# main.net
KiCad netlist of a schematic drawn in EAGLE
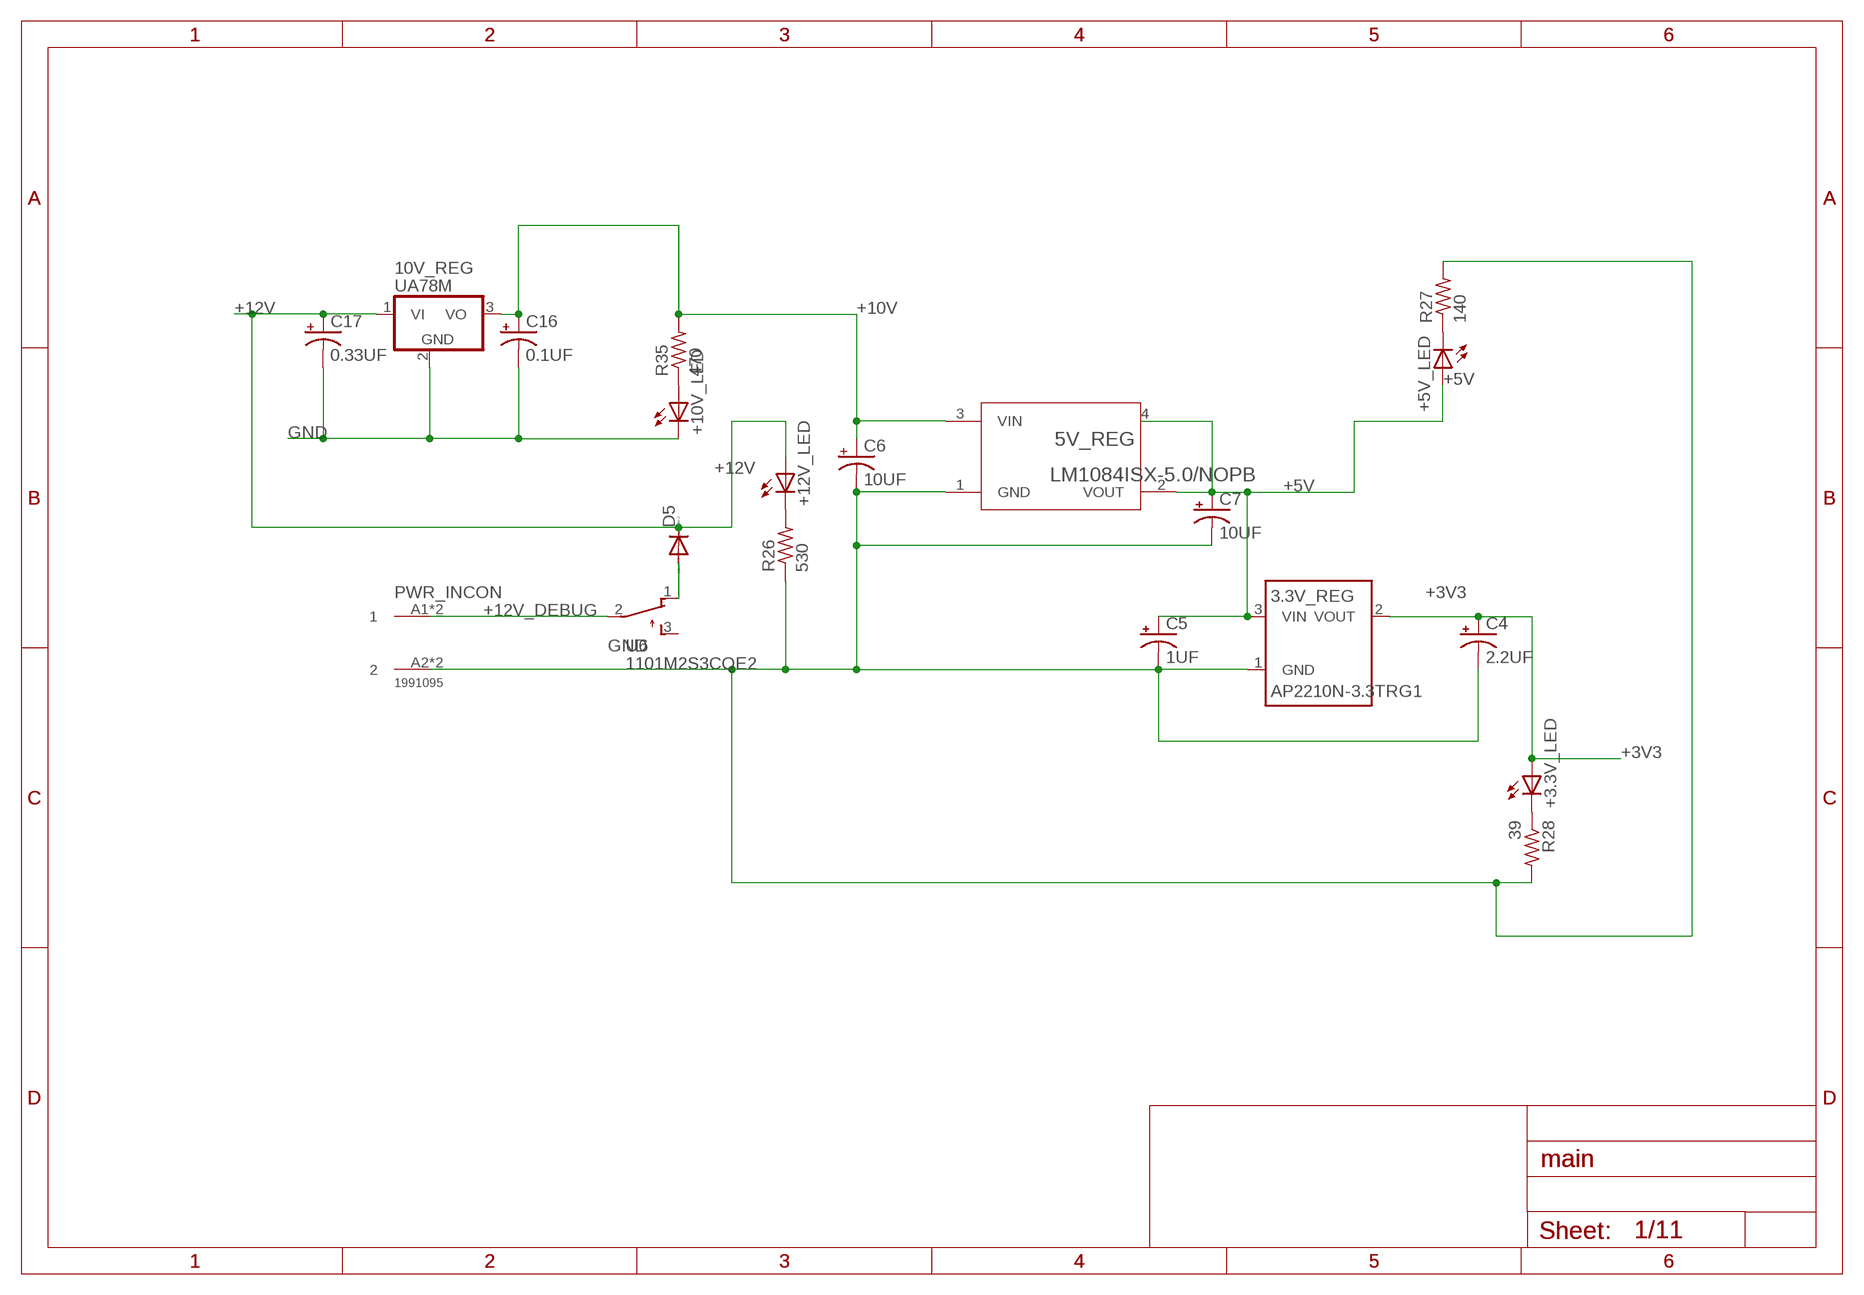
[diagram p0: schematic, sheet 1]
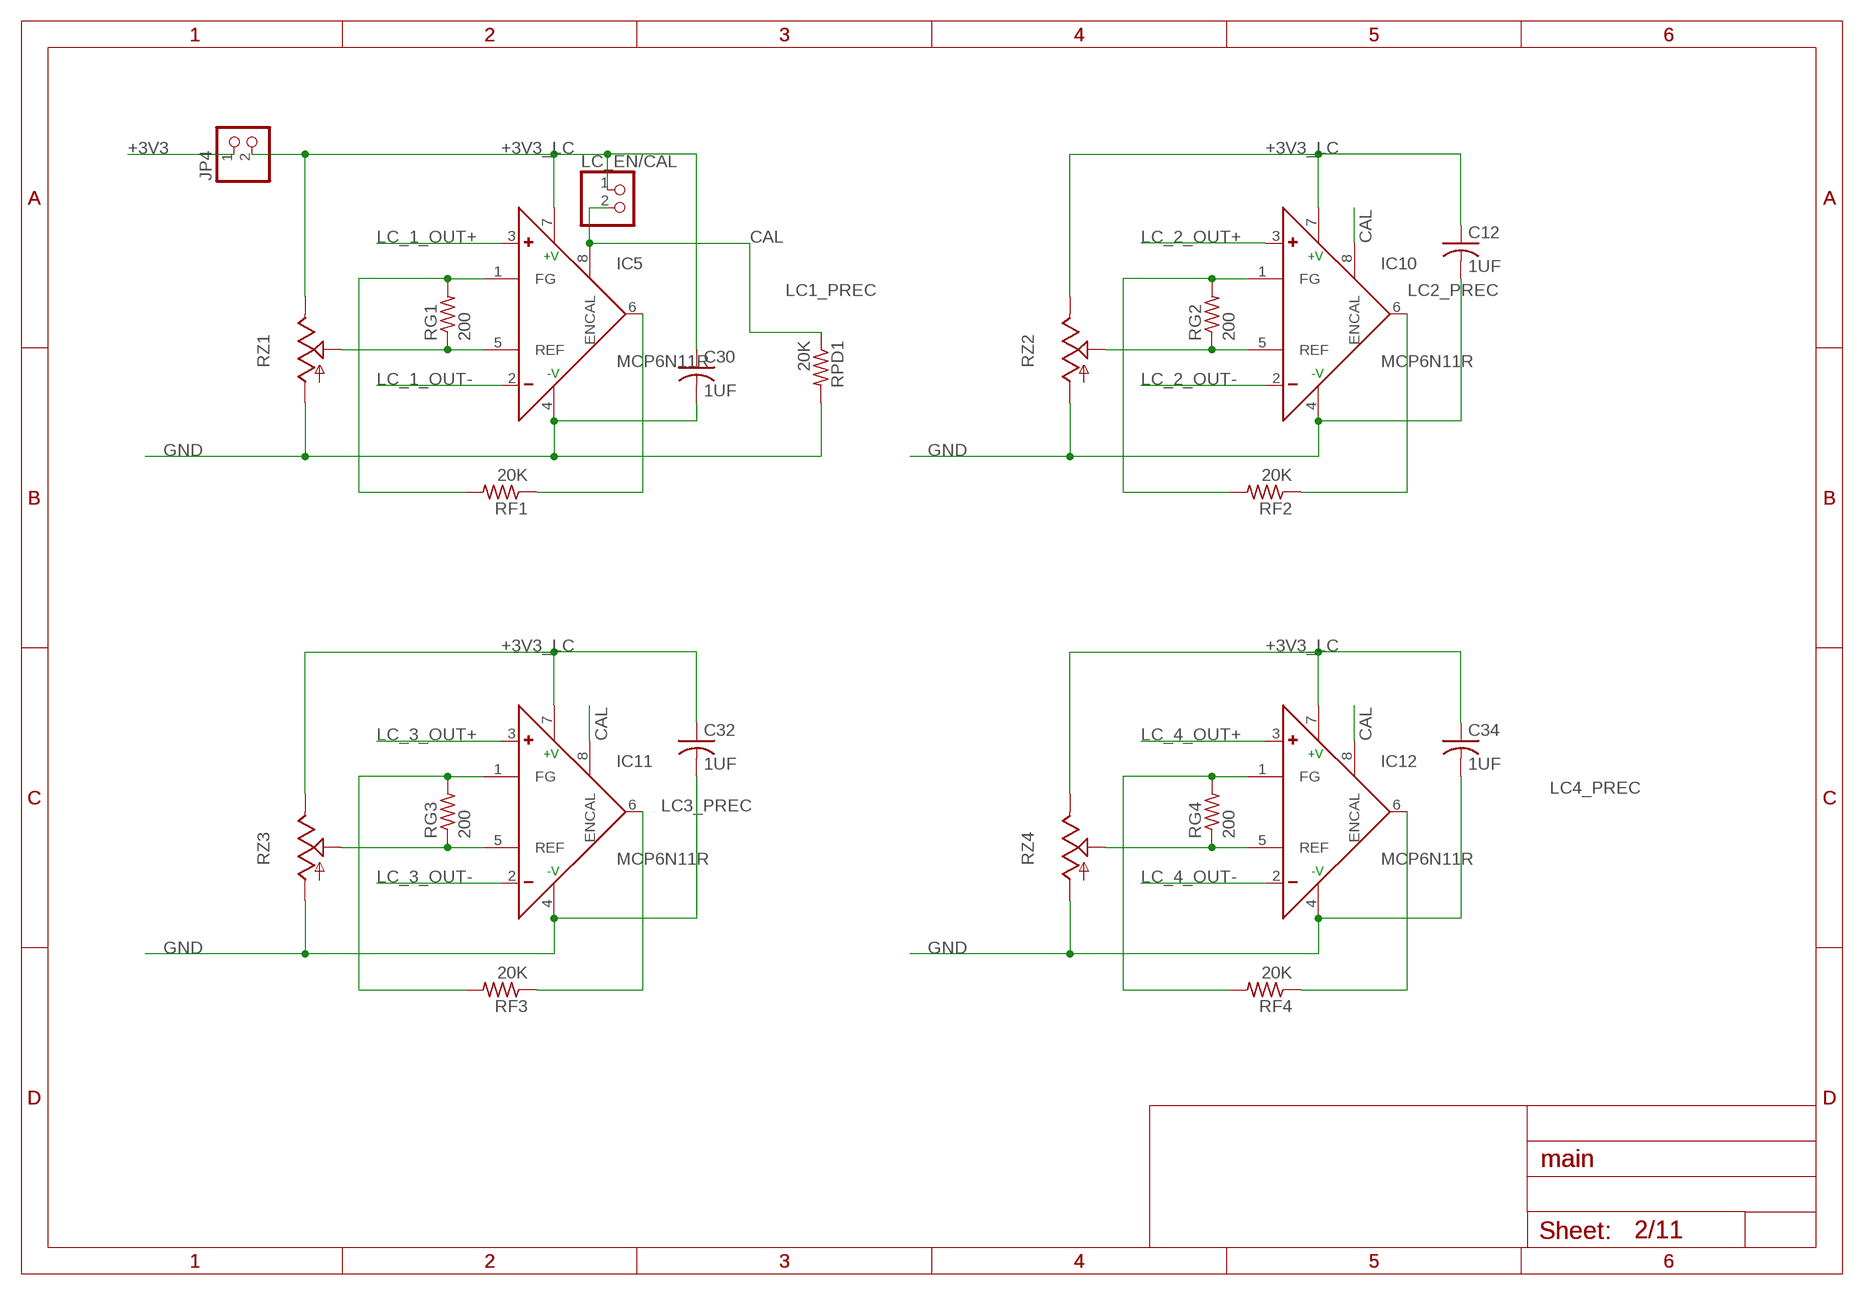
[diagram p1: schematic, sheet 2]
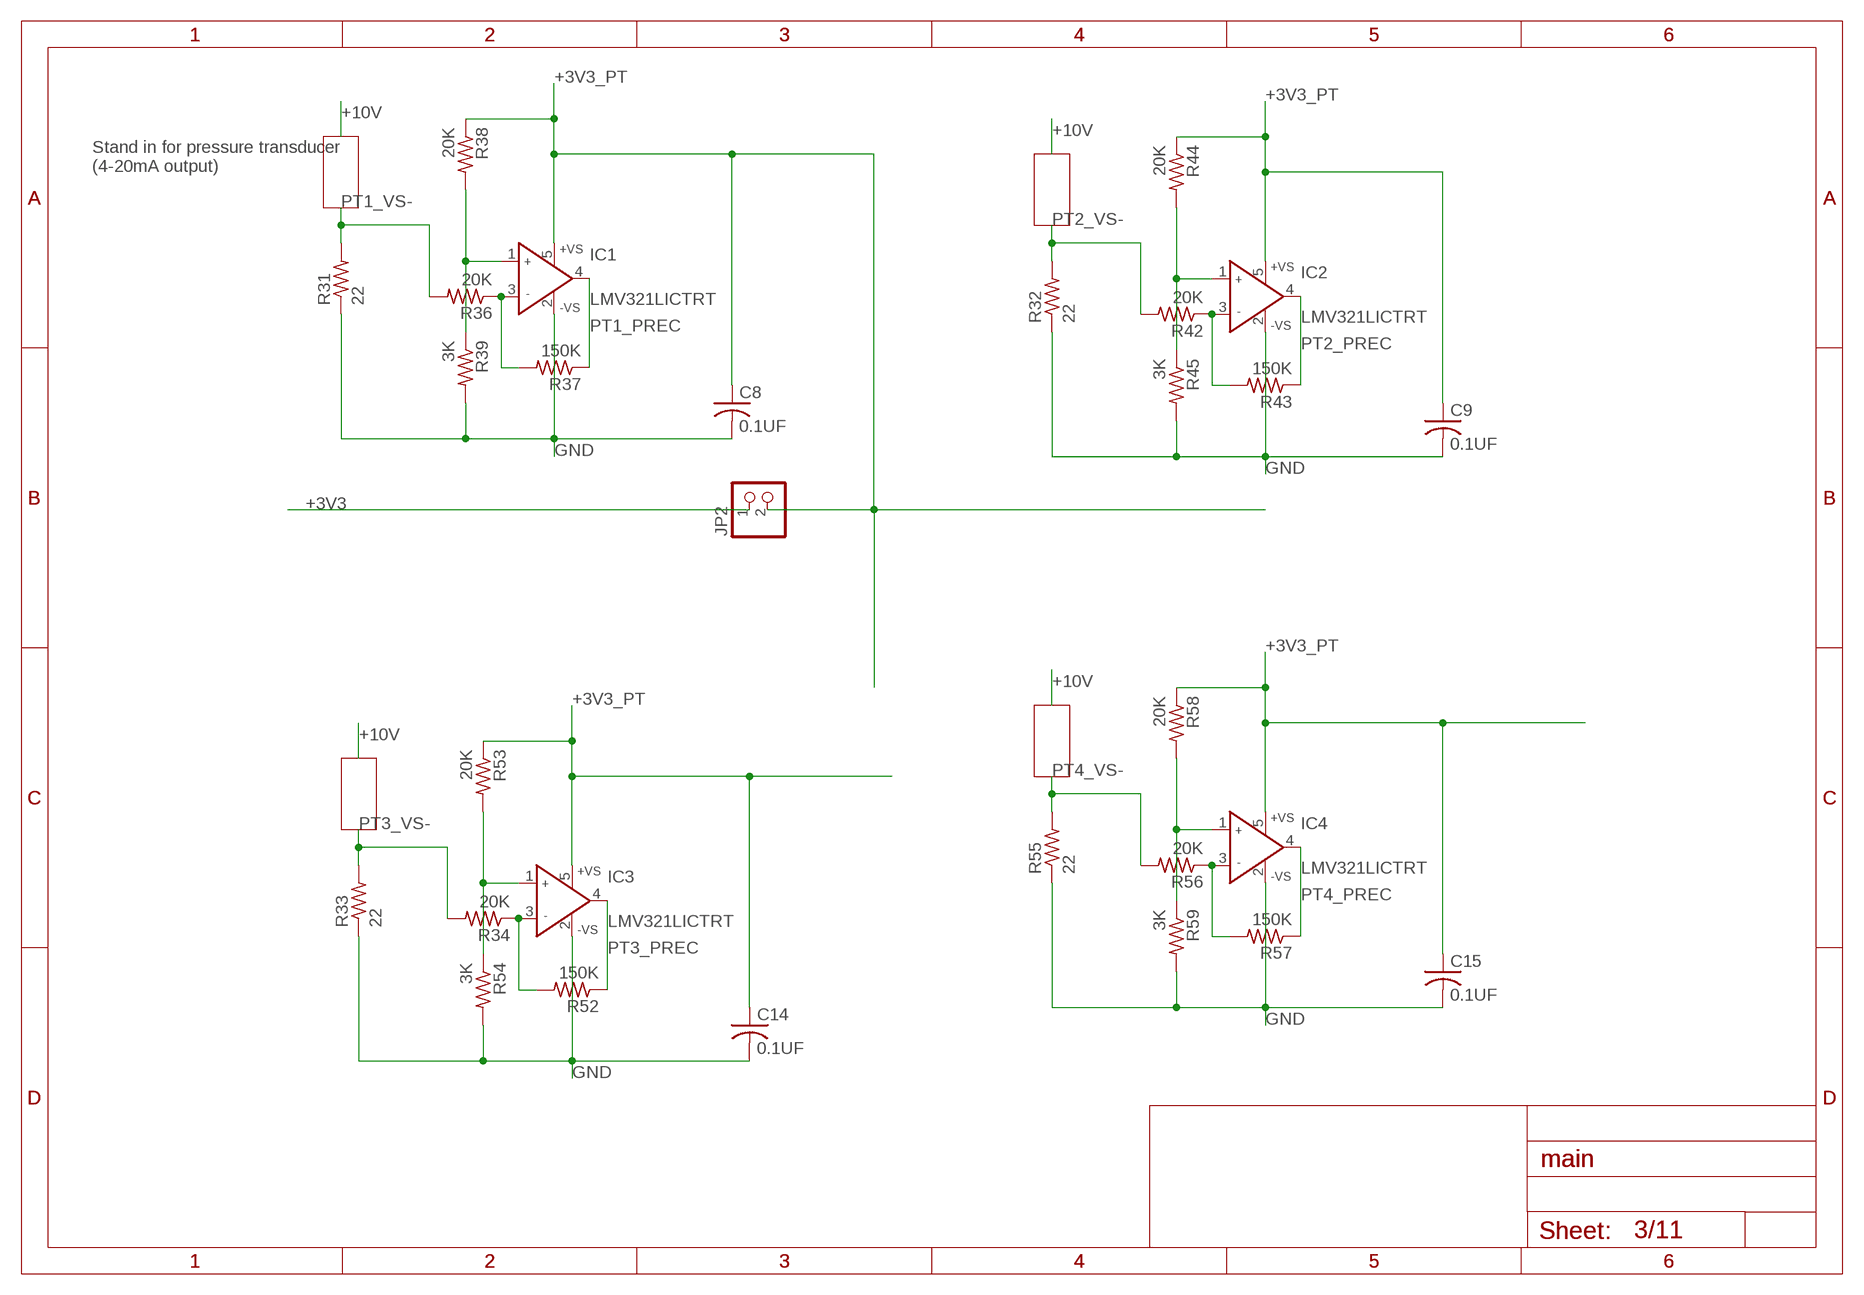
[diagram p2: schematic, sheet 3]
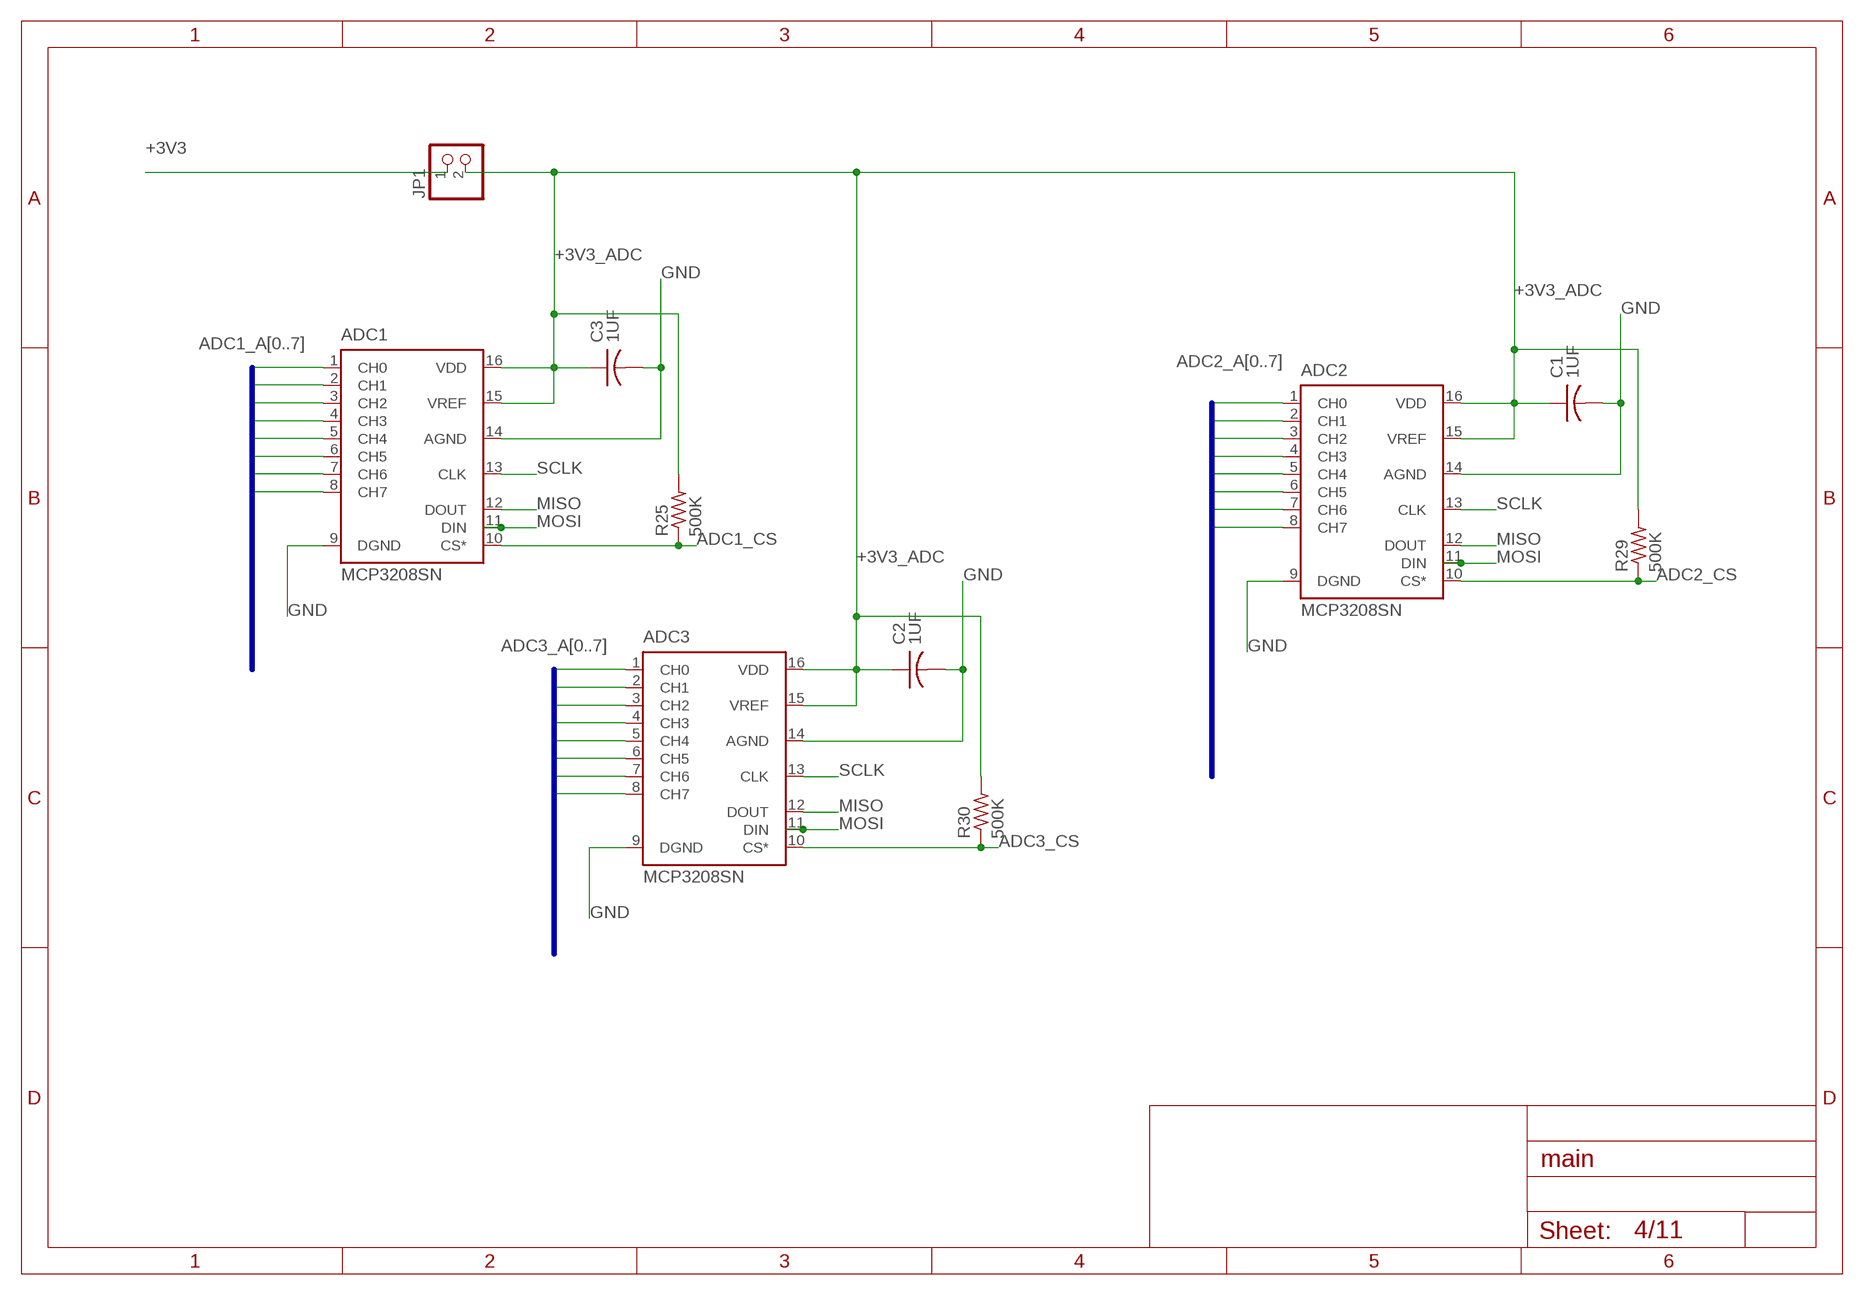
[diagram p3: schematic, sheet 4]
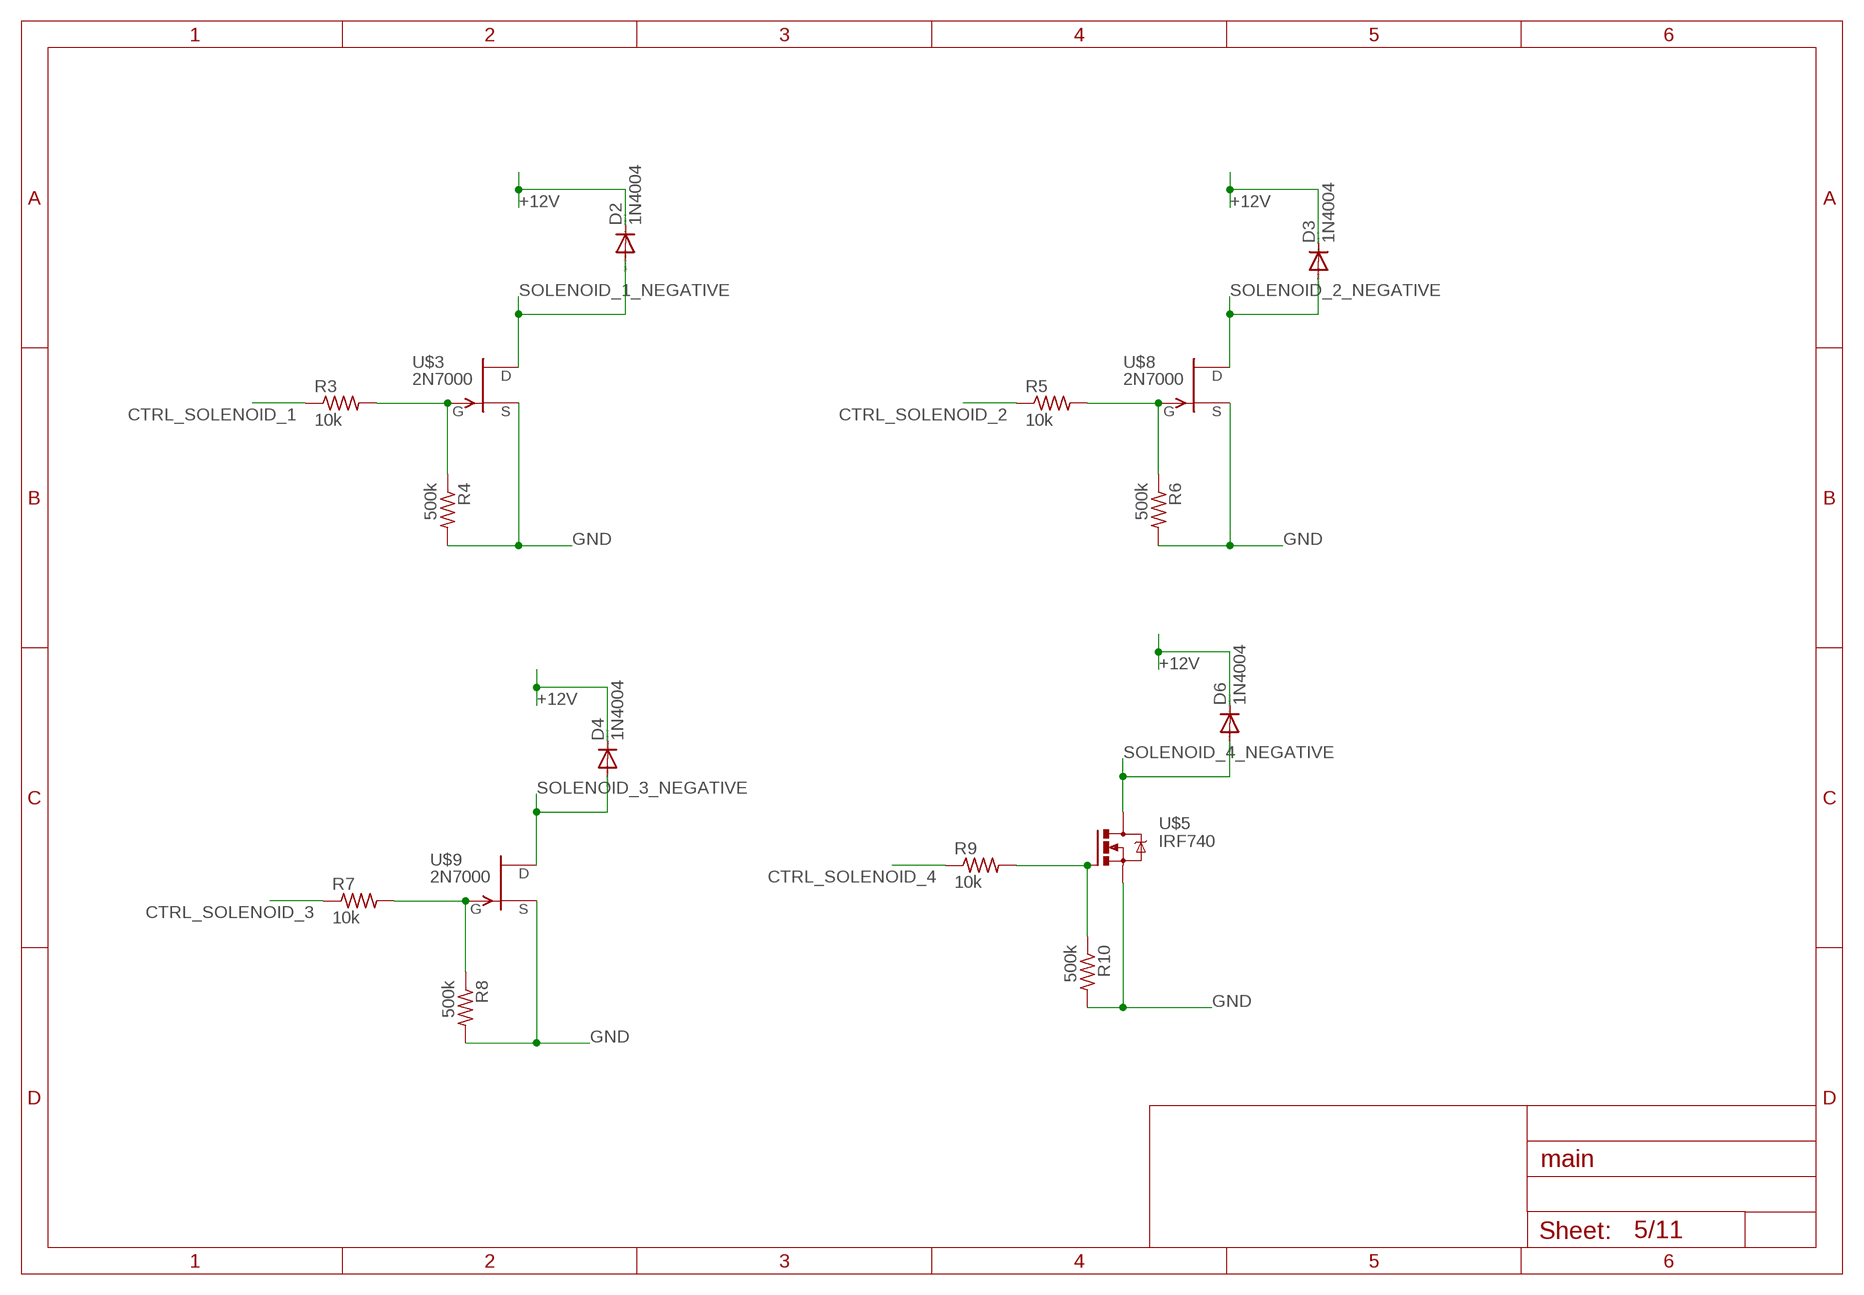
[diagram p4: schematic, sheet 5]
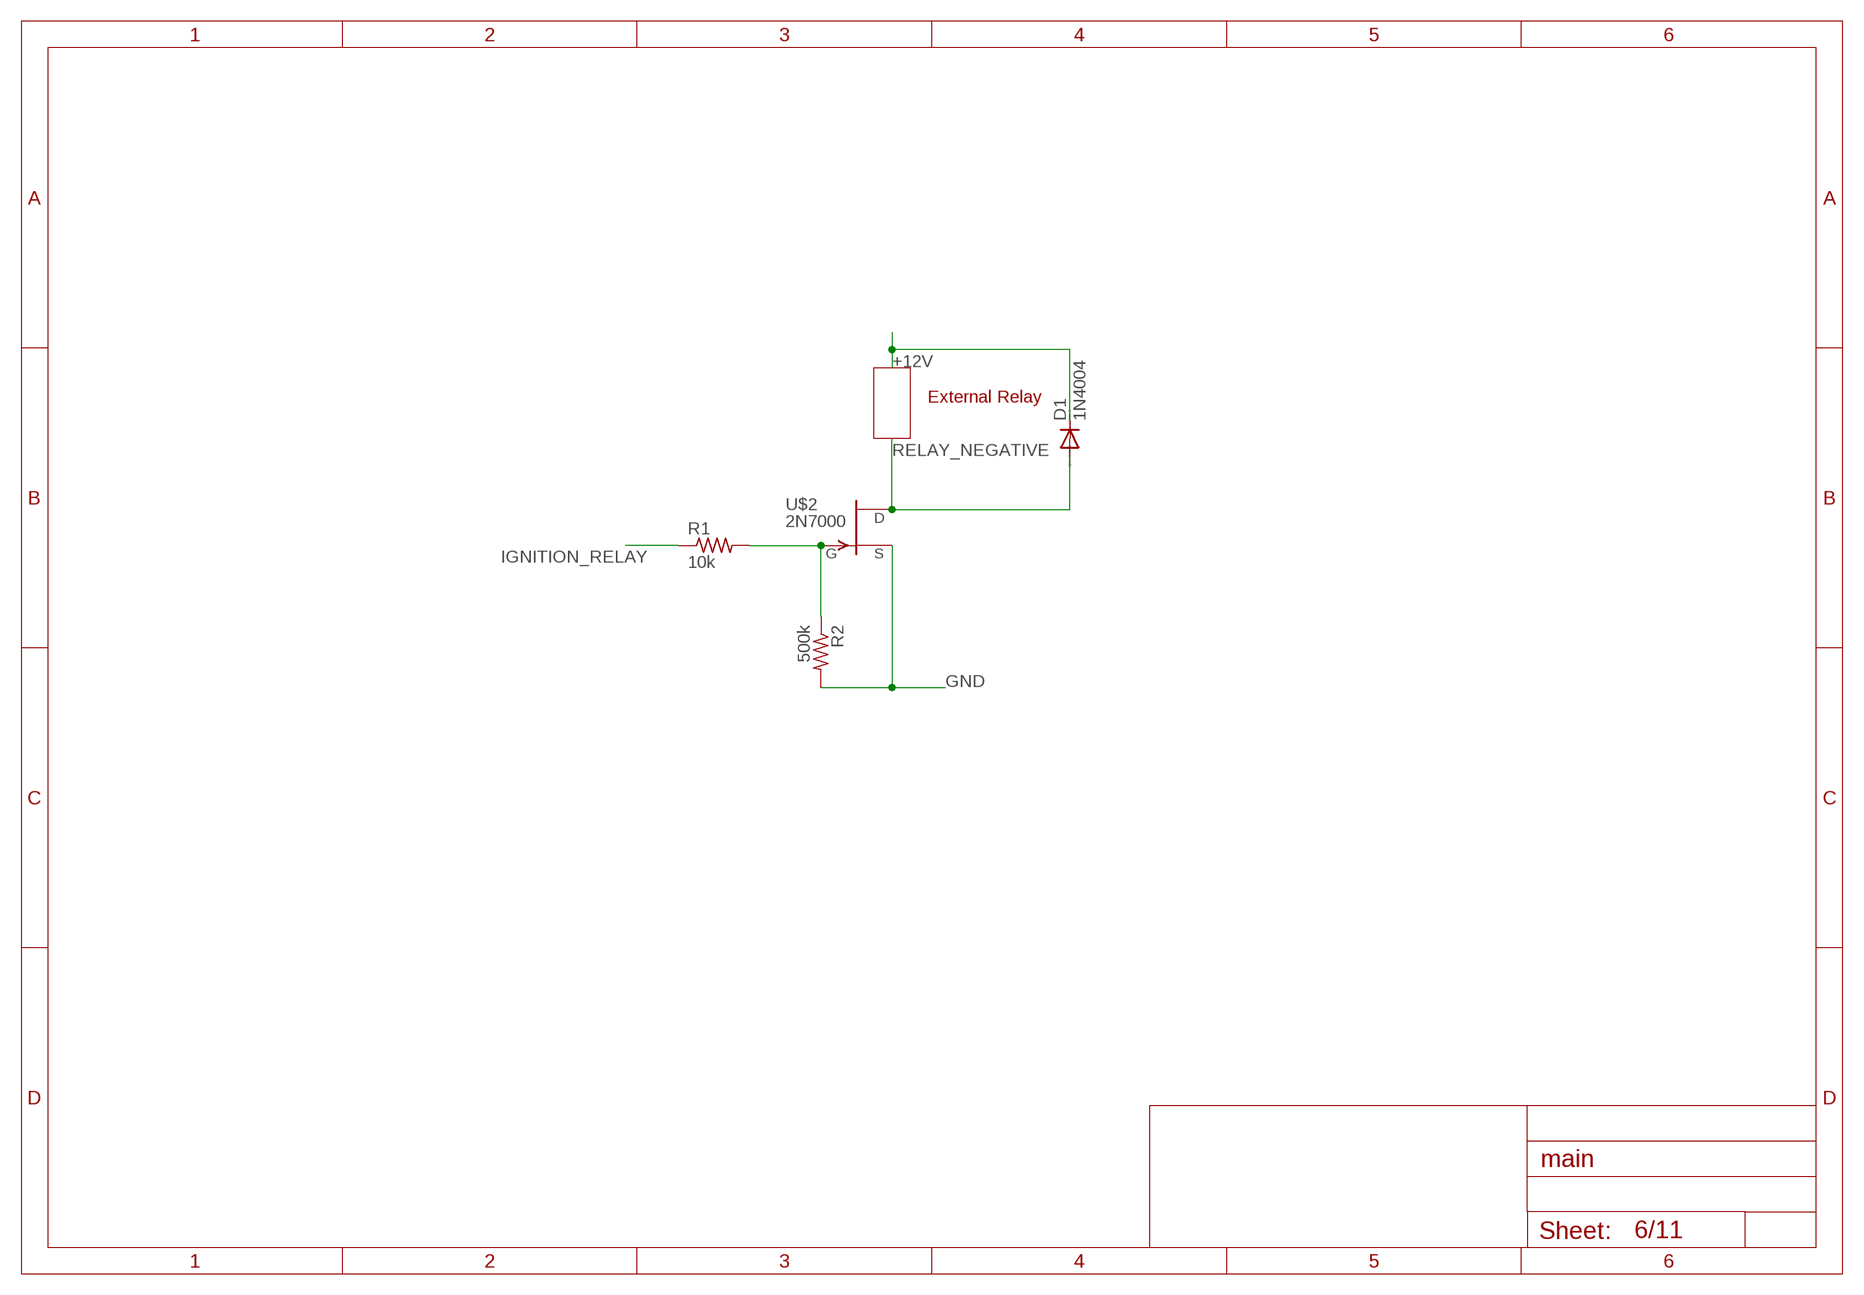
[diagram p5: schematic, sheet 6]
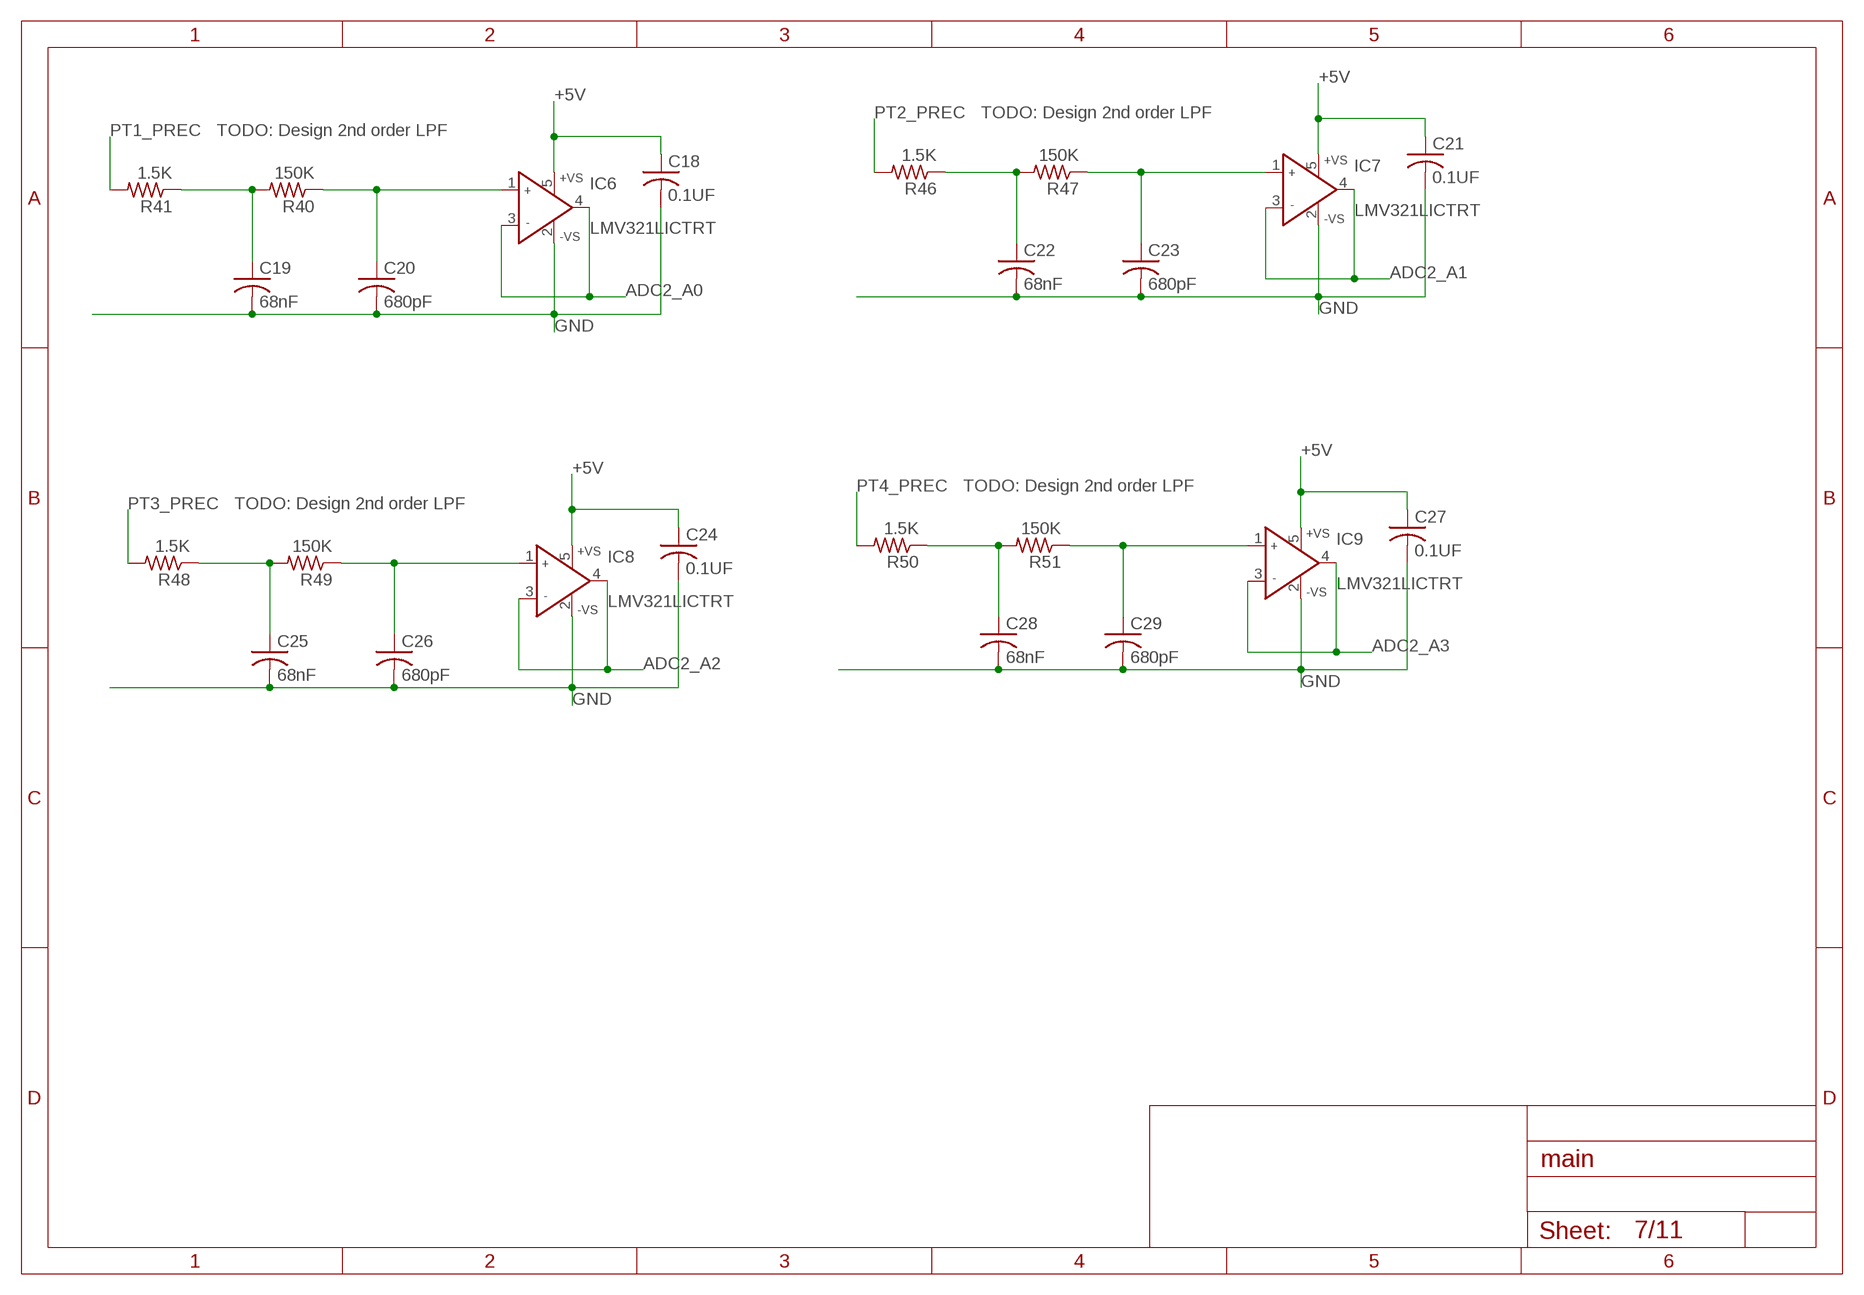
[diagram p6: schematic, sheet 7]
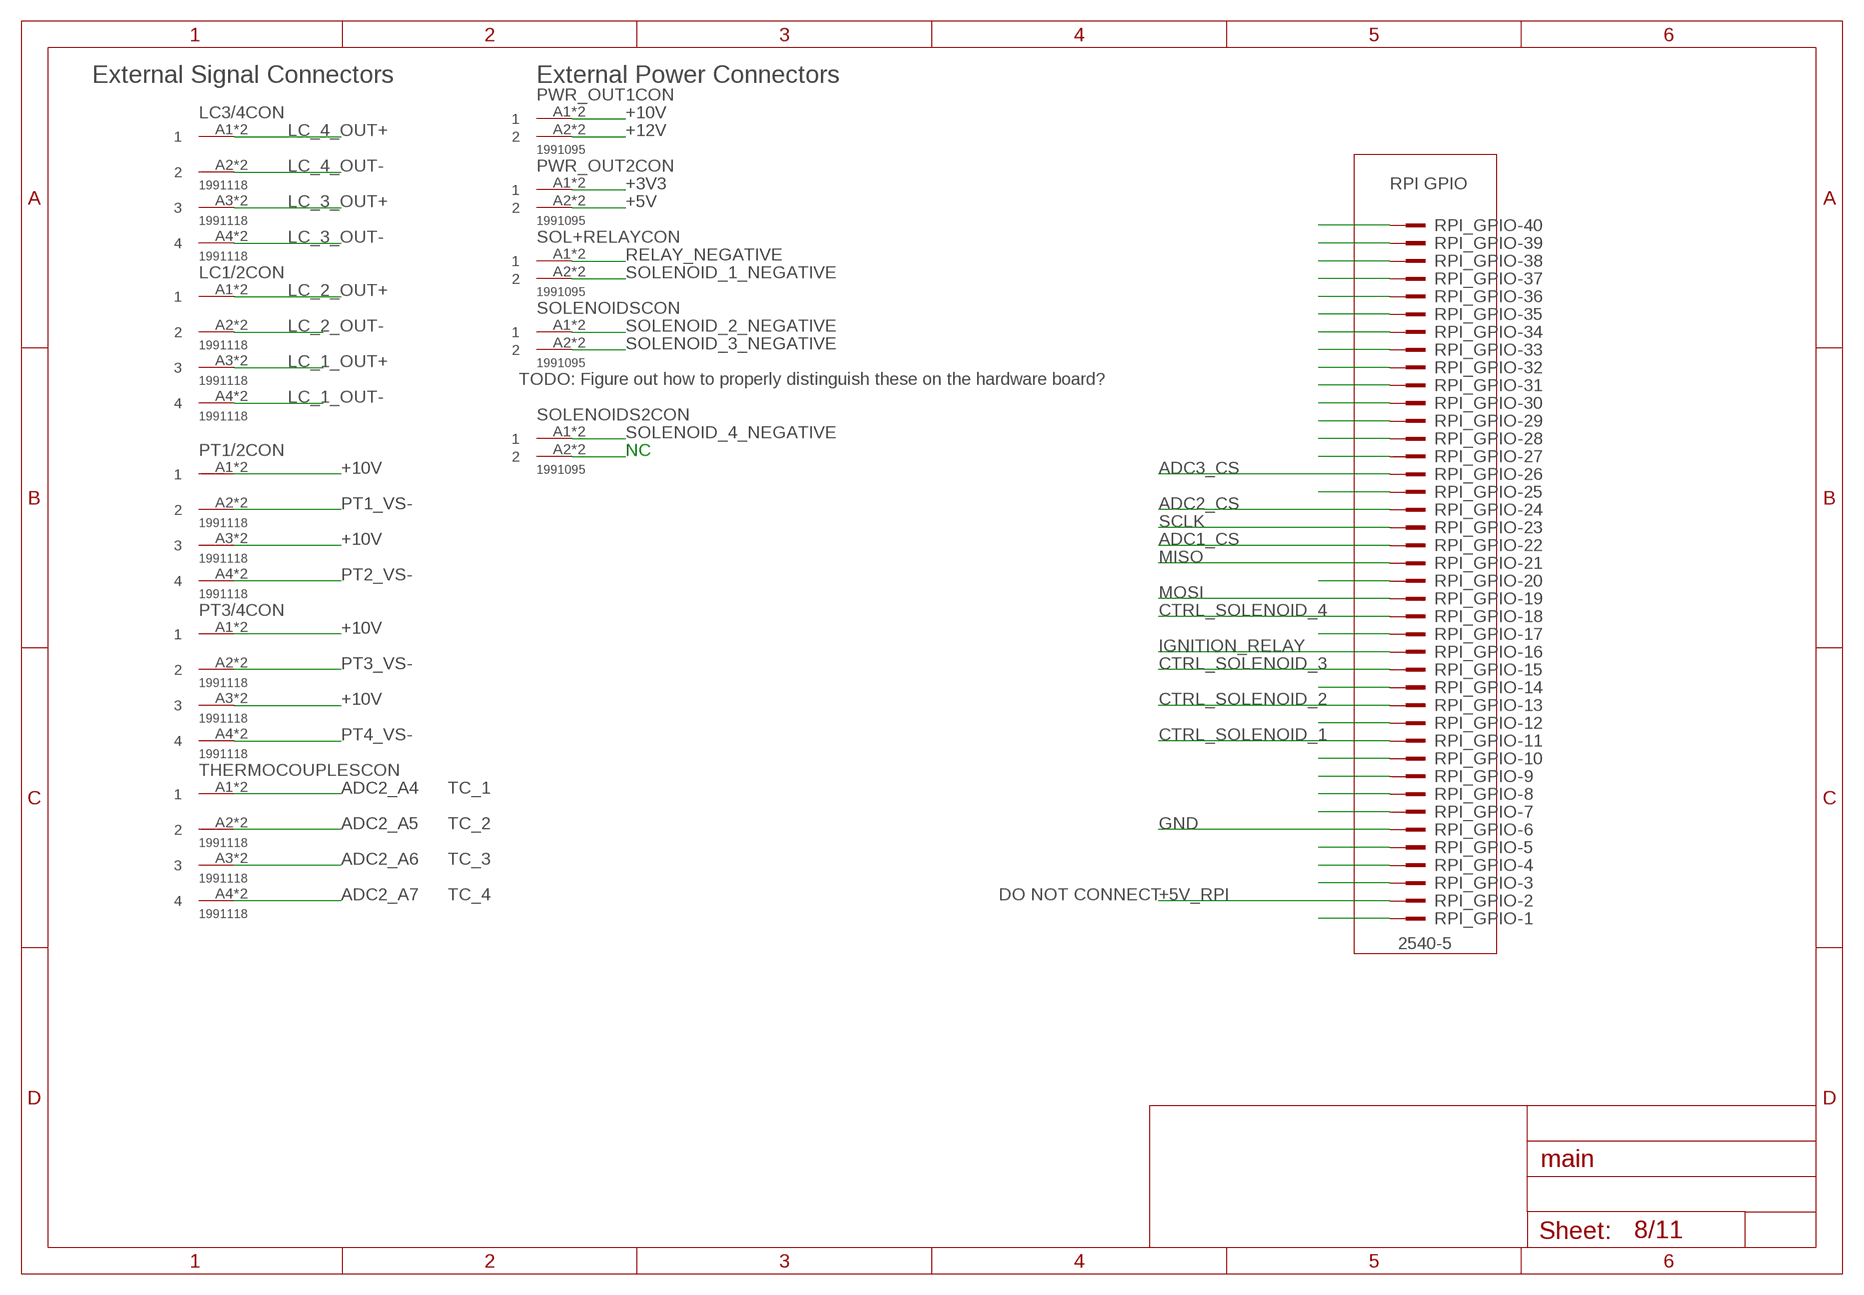
[diagram p7: schematic, sheet 8]
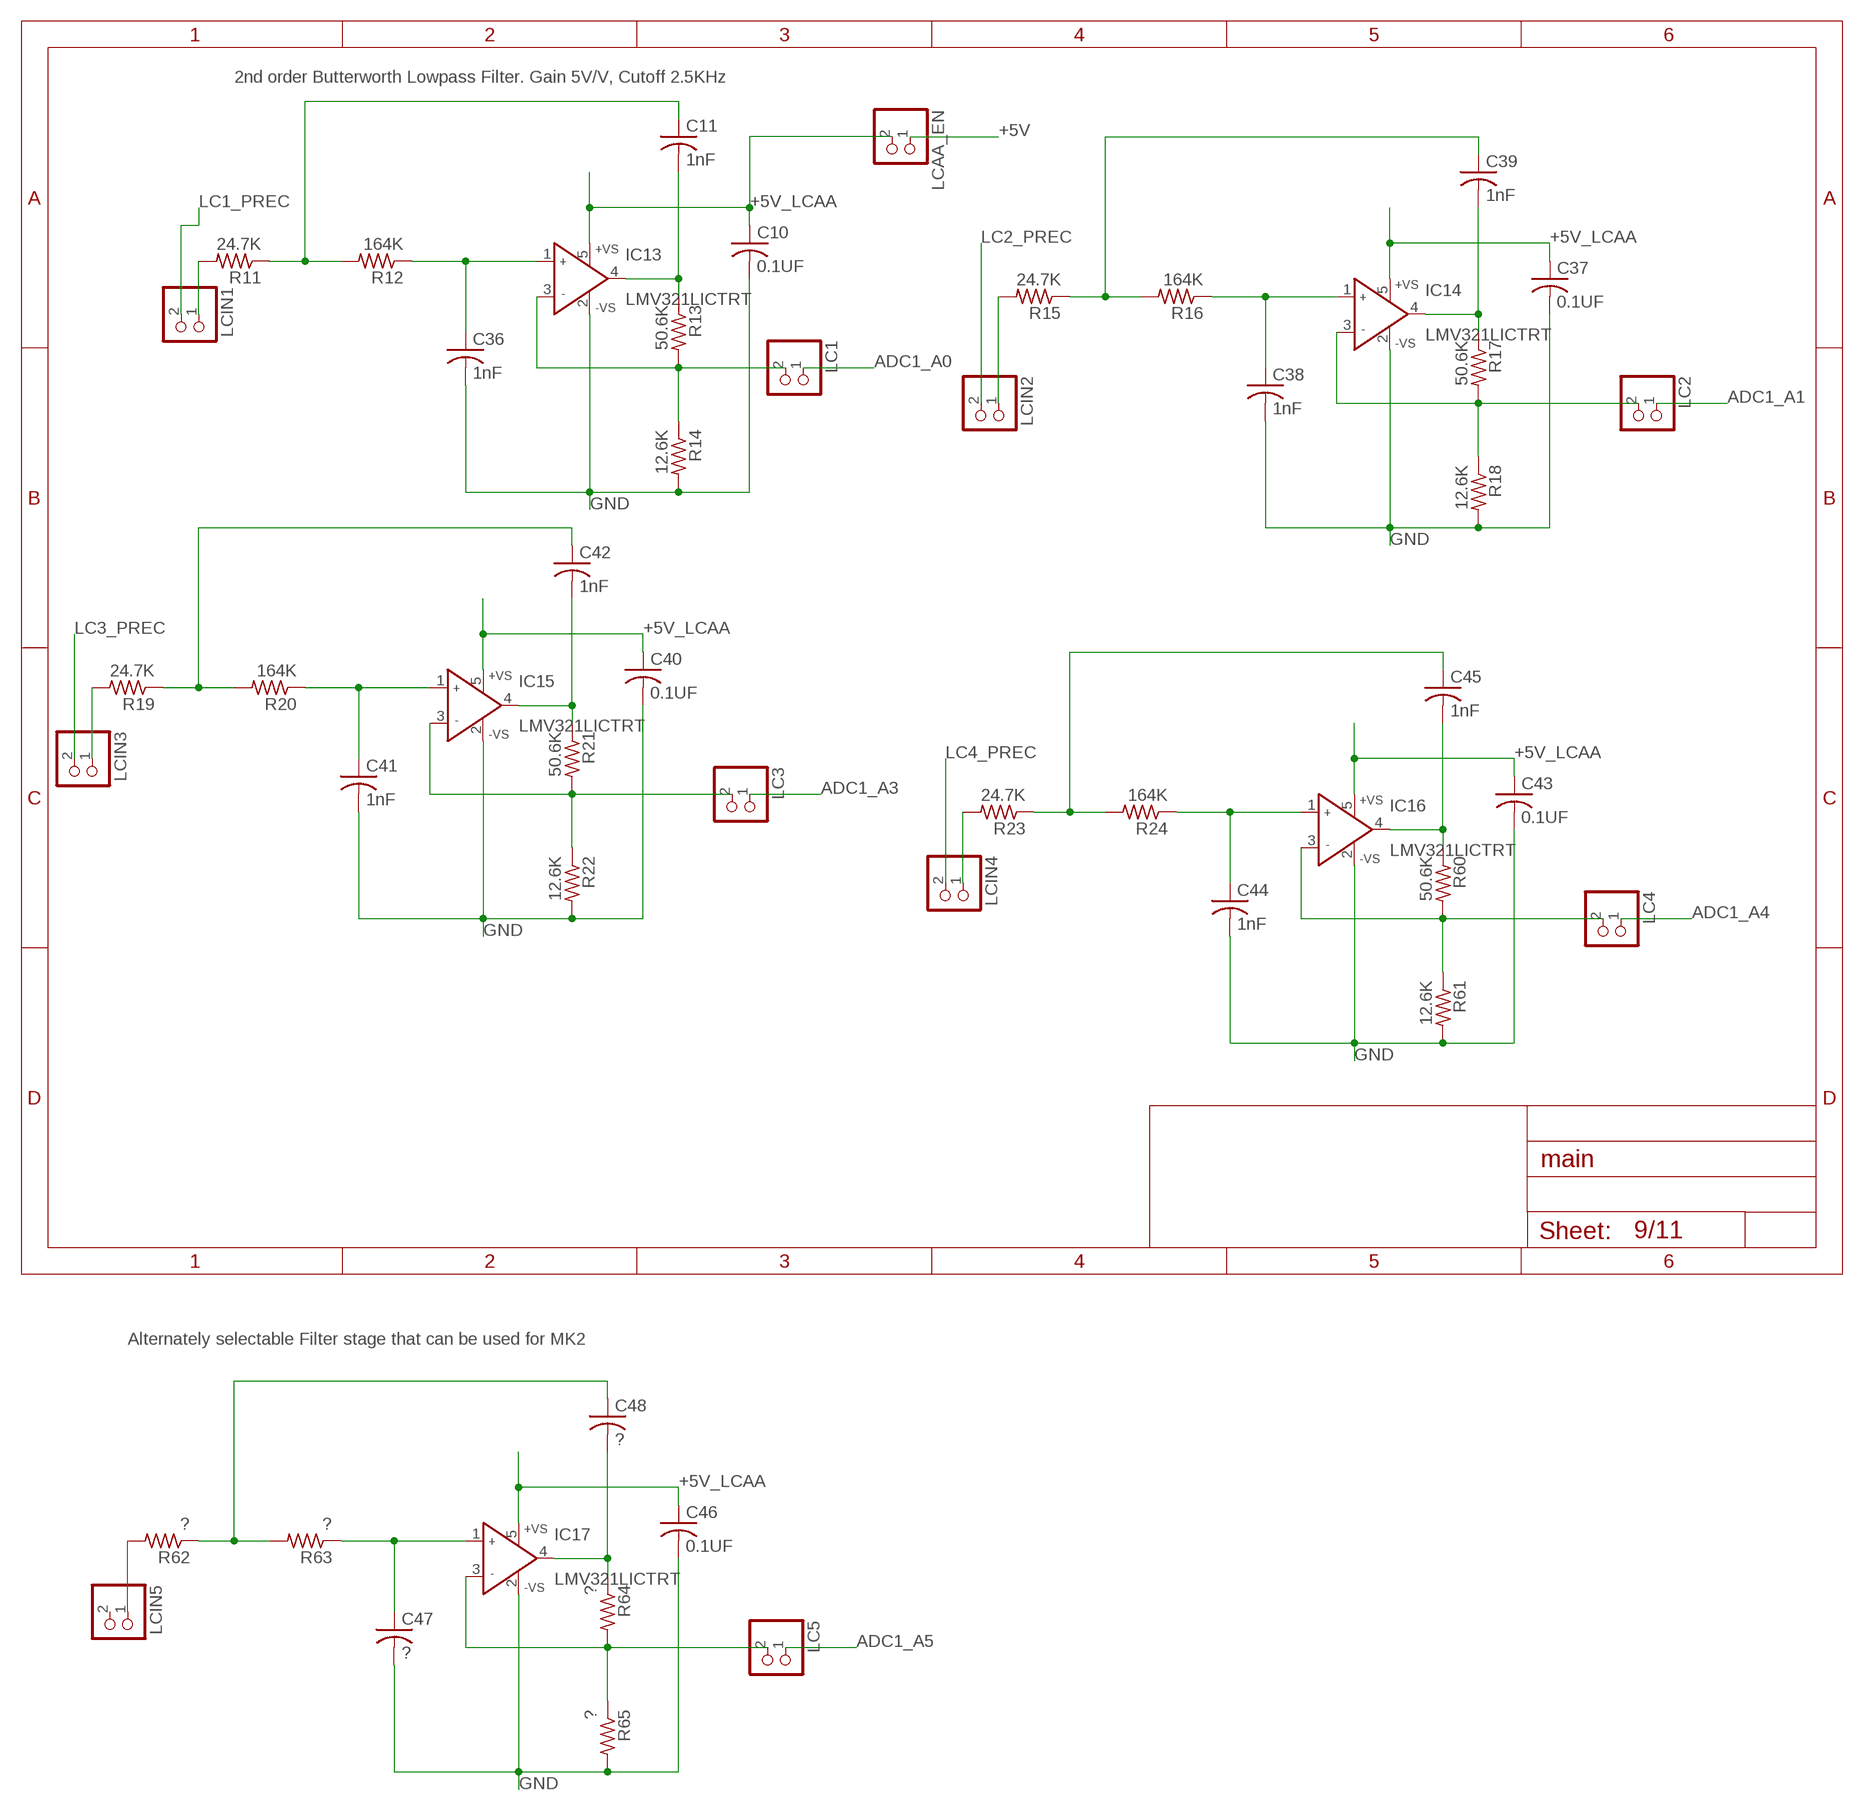
[diagram p8: schematic, sheet 9]
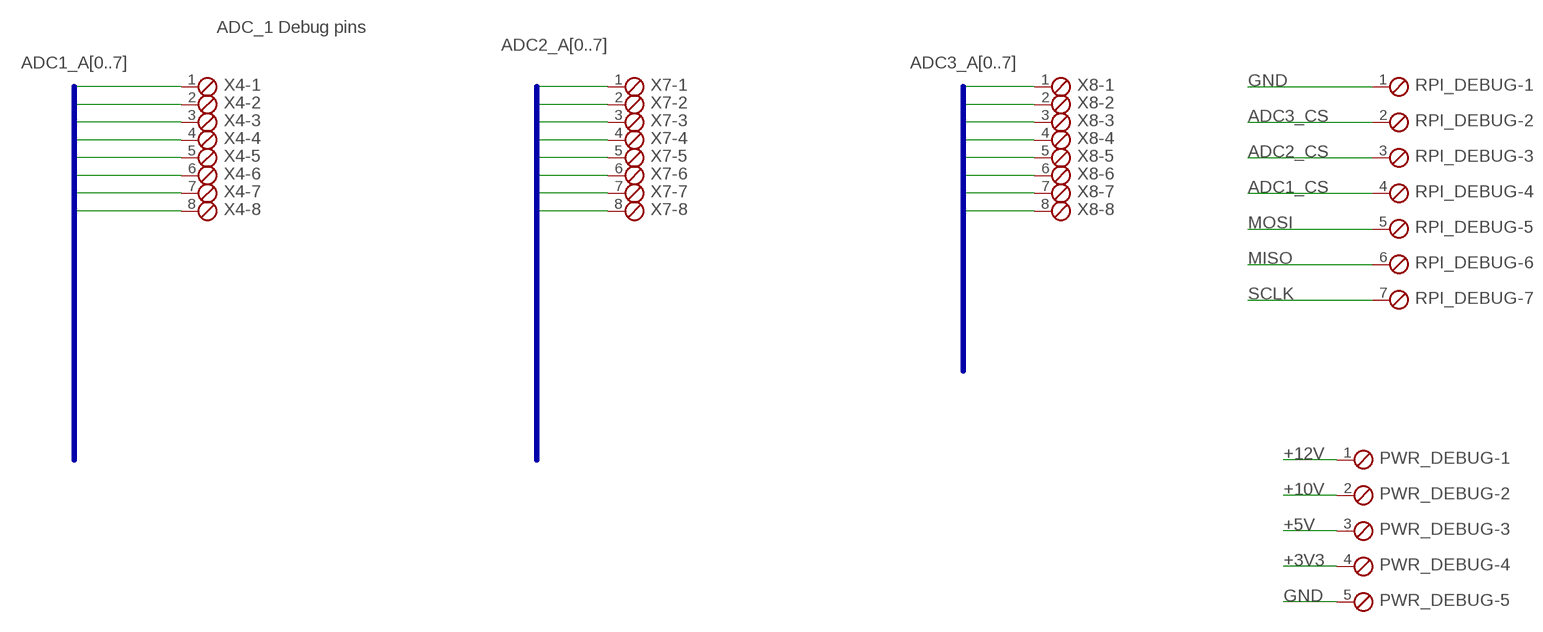
[diagram p9: schematic, sheet 10]

(export (version "E")
  (design (tool "Eeschema 10.0.6"))
  (components
    (comp (ref "LC1/2")
      (value "1991118")
      (footprint "eagle-import:1991118")
      (libsource (lib "eagle-import") (part "1991118"))
    )
    (comp (ref "LC3/4")
      (value "1991118")
      (footprint "eagle-import:1991118")
      (libsource (lib "eagle-import") (part "1991118"))
    )
    (comp (ref "PT1/2")
      (value "1991118")
      (footprint "eagle-import:1991118")
      (libsource (lib "eagle-import") (part "1991118"))
    )
    (comp (ref "PT3/4")
      (value "1991118")
      (footprint "eagle-import:1991118")
      (libsource (lib "eagle-import") (part "1991118"))
    )
    (comp (ref "PWR_OUT1")
      (value "1991095")
      (footprint "eagle-import:1991095")
      (libsource (lib "eagle-import") (part "1991095"))
    )
    (comp (ref "PWR_OUT2")
      (value "1991095")
      (footprint "eagle-import:1991095")
      (libsource (lib "eagle-import") (part "1991095"))
    )
    (comp (ref "RPI_GPIO")
      (value "2540-5")
      (footprint "eagle-import:PAK100_2500-5-40")
      (libsource (lib "eagle-import") (part "2540-5"))
    )
    (comp (ref "SOL+RELAY")
      (value "1991095")
      (footprint "eagle-import:1991095")
      (libsource (lib "eagle-import") (part "1991095"))
    )
    (comp (ref "SOLENOIDS")
      (value "1991095")
      (footprint "eagle-import:1991095")
      (libsource (lib "eagle-import") (part "1991095"))
    )
    (comp (ref "SOLENOIDS2")
      (value "1991095")
      (footprint "eagle-import:1991095")
      (libsource (lib "eagle-import") (part "1991095"))
    )
    (comp (ref "THERMOCOUPLES")
      (value "1991118")
      (footprint "eagle-import:1991118")
      (libsource (lib "eagle-import") (part "1991118"))
    )
    (comp (ref "+3.3V_LED")
      (value "LED5MM")
      (footprint "eagle-import:LED5MM")
      (libsource (lib "eagle-import") (part "LED5MM"))
    )
    (comp (ref "+5V_LED")
      (value "LED5MM")
      (footprint "eagle-import:LED5MM")
      (libsource (lib "eagle-import") (part "LED5MM"))
    )
    (comp (ref "+10V_LED")
      (value "LED5MM")
      (footprint "eagle-import:LED5MM")
      (libsource (lib "eagle-import") (part "LED5MM"))
    )
    (comp (ref "+12V_LED")
      (value "LED5MM")
      (footprint "eagle-import:LED5MM")
      (libsource (lib "eagle-import") (part "LED5MM"))
    )
    (comp (ref "3.3V_REG")
      (value "AP2210N-3.3TRG1")
      (footprint "eagle-import:SOT23")
      (libsource (lib "eagle-import") (part "AP2210N-3.3TRG1"))
    )
    (comp (ref "5V_REG")
      (value "LM1084ISX-5.0/NOPB")
      (footprint "eagle-import:TS3B")
      (fields (field (name "MANUFACTURER_PART_NUMBER") "LM1084ISX5.0NOPB"))
      (libsource (lib "eagle-import") (part "LM1084ISX-5.0/NOPB"))
    )
    (comp (ref "10V_REG")
      (value "UA78M")
      (footprint "eagle-import:TO220S")
      (libsource (lib "eagle-import") (part "UA78M"))
    )
    (comp (ref "C4")
      (value "2.2UF")
      (footprint "eagle-import:E2,5-5")
      (libsource (lib "eagle-import") (part "CPOL-USE2.5-5"))
    )
    (comp (ref "C5")
      (value "1UF")
      (footprint "eagle-import:E2,5-5")
      (libsource (lib "eagle-import") (part "CPOL-USE2.5-5"))
    )
    (comp (ref "C6")
      (value "10UF")
      (footprint "eagle-import:E2,5-5")
      (libsource (lib "eagle-import") (part "CPOL-USE2.5-5"))
    )
    (comp (ref "C7")
      (value "10UF")
      (footprint "eagle-import:E2,5-5")
      (libsource (lib "eagle-import") (part "CPOL-USE2.5-5"))
    )
    (comp (ref "C16")
      (value "0.1UF")
      (footprint "eagle-import:E2,5-5")
      (libsource (lib "eagle-import") (part "CPOL-USE2.5-5"))
    )
    (comp (ref "C17")
      (value "0.33UF")
      (footprint "eagle-import:E2,5-5")
      (libsource (lib "eagle-import") (part "CPOL-USE2.5-5"))
    )
    (comp (ref "D5")
      (value "DIODE-DO201-15")
      (footprint "eagle-import:DO201-15")
      (libsource (lib "eagle-import") (part "DIODE-DO201-15"))
    )
    (comp (ref "PWR_IN")
      (value "1991095")
      (footprint "eagle-import:1991095")
      (libsource (lib "eagle-import") (part "1991095"))
    )
    (comp (ref "R26")
      (value "530")
      (footprint "eagle-import:R0805")
      (libsource (lib "eagle-import") (part "resistor_348_R-US_R0805"))
    )
    (comp (ref "R27")
      (value "140")
      (footprint "eagle-import:R0805")
      (libsource (lib "eagle-import") (part "resistor_348_R-US_R0805"))
    )
    (comp (ref "R28")
      (value "39")
      (footprint "eagle-import:R0805")
      (libsource (lib "eagle-import") (part "resistor_348_R-US_R0805"))
    )
    (comp (ref "R35")
      (value "470")
      (footprint "eagle-import:R0805")
      (libsource (lib "eagle-import") (part "resistor_348_R-US_R0805"))
    )
    (comp (ref "U6")
      (value "1101M2S3CQE2")
      (footprint "eagle-import:1101M2S3CQE2")
      (fields (field (name "COPYRIGHT") "Copyright (C) 2015 Accelerated Designs. All rights reserved"))
      (libsource (lib "eagle-import") (part "1101M2S3CQE2"))
    )
    (comp (ref "ADC1")
      (value "MCP3208SN")
      (footprint "eagle-import:SO-16")
      (fields (field (name "MF") "MICROCHIP") (field (name "MPN") "MCP3202-CI/SN"))
      (libsource (lib "eagle-import") (part "MCP3208SN"))
    )
    (comp (ref "ADC2")
      (value "MCP3208SN")
      (footprint "eagle-import:SO-16")
      (fields (field (name "MF") "MICROCHIP") (field (name "MPN") "MCP3202-CI/SN"))
      (libsource (lib "eagle-import") (part "MCP3208SN"))
    )
    (comp (ref "ADC3")
      (value "MCP3208SN")
      (footprint "eagle-import:SO-16")
      (fields (field (name "MF") "MICROCHIP") (field (name "MPN") "MCP3202-CI/SN"))
      (libsource (lib "eagle-import") (part "MCP3208SN"))
    )
    (comp (ref "C1")
      (value "1UF")
      (footprint "eagle-import:C0805")
      (libsource (lib "eagle-import") (part "C-USC0805"))
    )
    (comp (ref "C2")
      (value "1UF")
      (footprint "eagle-import:C0805")
      (libsource (lib "eagle-import") (part "C-USC0805"))
    )
    (comp (ref "C3")
      (value "1UF")
      (footprint "eagle-import:C0805")
      (libsource (lib "eagle-import") (part "C-USC0805"))
    )
    (comp (ref "JP1")
      (value "PINHD-1X2")
      (footprint "eagle-import:1X02")
      (libsource (lib "eagle-import") (part "PINHD-1X2"))
    )
    (comp (ref "R25")
      (value "500K")
      (footprint "eagle-import:R0805")
      (libsource (lib "eagle-import") (part "R-US_R0805"))
    )
    (comp (ref "R29")
      (value "500K")
      (footprint "eagle-import:R0805")
      (libsource (lib "eagle-import") (part "R-US_R0805"))
    )
    (comp (ref "R30")
      (value "500K")
      (footprint "eagle-import:R0805")
      (libsource (lib "eagle-import") (part "R-US_R0805"))
    )
    (comp (ref "C12")
      (value "1UF")
      (footprint "eagle-import:C0805")
      (libsource (lib "eagle-import") (part "C-USC0805"))
    )
    (comp (ref "C30")
      (value "1UF")
      (footprint "eagle-import:C0805")
      (libsource (lib "eagle-import") (part "C-USC0805"))
    )
    (comp (ref "C32")
      (value "1UF")
      (footprint "eagle-import:C0805")
      (libsource (lib "eagle-import") (part "C-USC0805"))
    )
    (comp (ref "C34")
      (value "1UF")
      (footprint "eagle-import:C0805")
      (libsource (lib "eagle-import") (part "C-USC0805"))
    )
    (comp (ref "IC5")
      (value "MCP6N11R")
      (footprint "eagle-import:SO-8")
      (fields (field (name "MPN") "AD620AR"))
      (libsource (lib "eagle-import") (part "MCP6N11R"))
    )
    (comp (ref "IC10")
      (value "MCP6N11R")
      (footprint "eagle-import:SO-8")
      (fields (field (name "MPN") "AD620AR"))
      (libsource (lib "eagle-import") (part "MCP6N11R"))
    )
    (comp (ref "IC11")
      (value "MCP6N11R")
      (footprint "eagle-import:SO-8")
      (fields (field (name "MPN") "AD620AR"))
      (libsource (lib "eagle-import") (part "MCP6N11R"))
    )
    (comp (ref "IC12")
      (value "MCP6N11R")
      (footprint "eagle-import:SO-8")
      (fields (field (name "MPN") "AD620AR"))
      (libsource (lib "eagle-import") (part "MCP6N11R"))
    )
    (comp (ref "JP4")
      (value "PINHD-1X2")
      (footprint "eagle-import:1X02")
      (libsource (lib "eagle-import") (part "PINHD-1X2"))
    )
    (comp (ref "LC_EN/CAL")
      (value "PINHD-1X2")
      (footprint "eagle-import:1X02")
      (libsource (lib "eagle-import") (part "PINHD-1X2"))
    )
    (comp (ref "RF1")
      (value "20K")
      (footprint "eagle-import:R0805")
      (libsource (lib "eagle-import") (part "R-US_R0805"))
    )
    (comp (ref "RF2")
      (value "20K")
      (footprint "eagle-import:R0805")
      (libsource (lib "eagle-import") (part "R-US_R0805"))
    )
    (comp (ref "RF3")
      (value "20K")
      (footprint "eagle-import:R0805")
      (libsource (lib "eagle-import") (part "R-US_R0805"))
    )
    (comp (ref "RF4")
      (value "20K")
      (footprint "eagle-import:R0805")
      (libsource (lib "eagle-import") (part "R-US_R0805"))
    )
    (comp (ref "RG1")
      (value "200")
      (footprint "eagle-import:R0805")
      (libsource (lib "eagle-import") (part "R-US_R0805"))
    )
    (comp (ref "RG2")
      (value "200")
      (footprint "eagle-import:R0805")
      (libsource (lib "eagle-import") (part "R-US_R0805"))
    )
    (comp (ref "RG3")
      (value "200")
      (footprint "eagle-import:R0805")
      (libsource (lib "eagle-import") (part "R-US_R0805"))
    )
    (comp (ref "RG4")
      (value "200")
      (footprint "eagle-import:R0805")
      (libsource (lib "eagle-import") (part "R-US_R0805"))
    )
    (comp (ref "RPD1")
      (value "20K")
      (footprint "eagle-import:R0805")
      (libsource (lib "eagle-import") (part "R-US_R0805"))
    )
    (comp (ref "RZ1")
      (value "TRIM_US-S64W")
      (footprint "eagle-import:S64W")
      (libsource (lib "eagle-import") (part "TRIM_US-S64W"))
    )
    (comp (ref "RZ2")
      (value "TRIM_US-S64W")
      (footprint "eagle-import:S64W")
      (libsource (lib "eagle-import") (part "TRIM_US-S64W"))
    )
    (comp (ref "RZ3")
      (value "TRIM_US-S64W")
      (footprint "eagle-import:S64W")
      (libsource (lib "eagle-import") (part "TRIM_US-S64W"))
    )
    (comp (ref "RZ4")
      (value "TRIM_US-S64W")
      (footprint "eagle-import:S64W")
      (libsource (lib "eagle-import") (part "TRIM_US-S64W"))
    )
    (comp (ref "C18")
      (value "0.1UF")
      (footprint "eagle-import:C0805")
      (libsource (lib "eagle-import") (part "C-USC0805"))
    )
    (comp (ref "C19")
      (value "68nF")
      (footprint "eagle-import:C0805")
      (libsource (lib "eagle-import") (part "C-USC0805"))
    )
    (comp (ref "C20")
      (value "680pF")
      (footprint "eagle-import:C0805")
      (libsource (lib "eagle-import") (part "C-USC0805"))
    )
    (comp (ref "C21")
      (value "0.1UF")
      (footprint "eagle-import:C0805")
      (libsource (lib "eagle-import") (part "C-USC0805"))
    )
    (comp (ref "C22")
      (value "68nF")
      (footprint "eagle-import:C0805")
      (libsource (lib "eagle-import") (part "C-USC0805"))
    )
    (comp (ref "C23")
      (value "680pF")
      (footprint "eagle-import:C0805")
      (libsource (lib "eagle-import") (part "C-USC0805"))
    )
    (comp (ref "C24")
      (value "0.1UF")
      (footprint "eagle-import:C0805")
      (libsource (lib "eagle-import") (part "C-USC0805"))
    )
    (comp (ref "C25")
      (value "68nF")
      (footprint "eagle-import:C0805")
      (libsource (lib "eagle-import") (part "C-USC0805"))
    )
    (comp (ref "C26")
      (value "680pF")
      (footprint "eagle-import:C0805")
      (libsource (lib "eagle-import") (part "C-USC0805"))
    )
    (comp (ref "C27")
      (value "0.1UF")
      (footprint "eagle-import:C0805")
      (libsource (lib "eagle-import") (part "C-USC0805"))
    )
    (comp (ref "C28")
      (value "68nF")
      (footprint "eagle-import:C0805")
      (libsource (lib "eagle-import") (part "C-USC0805"))
    )
    (comp (ref "C29")
      (value "680pF")
      (footprint "eagle-import:C0805")
      (libsource (lib "eagle-import") (part "C-USC0805"))
    )
    (comp (ref "IC6")
      (value "LMV321LICTRT")
      (footprint "eagle-import:SOT23-5")
      (fields (field (name "MF") "ALTERA CORPORATION") (field (name "MPN") "AD8065ARTZ-REEL7"))
      (libsource (lib "eagle-import") (part "LMV321LICTRT"))
    )
    (comp (ref "IC7")
      (value "LMV321LICTRT")
      (footprint "eagle-import:SOT23-5")
      (fields (field (name "MF") "ALTERA CORPORATION") (field (name "MPN") "AD8065ARTZ-REEL7"))
      (libsource (lib "eagle-import") (part "LMV321LICTRT"))
    )
    (comp (ref "IC8")
      (value "LMV321LICTRT")
      (footprint "eagle-import:SOT23-5")
      (fields (field (name "MF") "ALTERA CORPORATION") (field (name "MPN") "AD8065ARTZ-REEL7"))
      (libsource (lib "eagle-import") (part "LMV321LICTRT"))
    )
    (comp (ref "IC9")
      (value "LMV321LICTRT")
      (footprint "eagle-import:SOT23-5")
      (fields (field (name "MF") "ALTERA CORPORATION") (field (name "MPN") "AD8065ARTZ-REEL7"))
      (libsource (lib "eagle-import") (part "LMV321LICTRT"))
    )
    (comp (ref "R40")
      (value "150K")
      (footprint "eagle-import:R0805")
      (libsource (lib "eagle-import") (part "R-US_R0805"))
    )
    (comp (ref "R41")
      (value "1.5K")
      (footprint "eagle-import:R0805")
      (libsource (lib "eagle-import") (part "R-US_R0805"))
    )
    (comp (ref "R46")
      (value "1.5K")
      (footprint "eagle-import:R0805")
      (libsource (lib "eagle-import") (part "R-US_R0805"))
    )
    (comp (ref "R47")
      (value "150K")
      (footprint "eagle-import:R0805")
      (libsource (lib "eagle-import") (part "R-US_R0805"))
    )
    (comp (ref "R48")
      (value "1.5K")
      (footprint "eagle-import:R0805")
      (libsource (lib "eagle-import") (part "R-US_R0805"))
    )
    (comp (ref "R49")
      (value "150K")
      (footprint "eagle-import:R0805")
      (libsource (lib "eagle-import") (part "R-US_R0805"))
    )
    (comp (ref "R50")
      (value "1.5K")
      (footprint "eagle-import:R0805")
      (libsource (lib "eagle-import") (part "R-US_R0805"))
    )
    (comp (ref "R51")
      (value "150K")
      (footprint "eagle-import:R0805")
      (libsource (lib "eagle-import") (part "R-US_R0805"))
    )
    (comp (ref "PWR_DEBUG")
      (value "MPT5")
      (footprint "eagle-import:5POL254")
      (libsource (lib "eagle-import") (part "MPT5"))
    )
    (comp (ref "RPI_DEBUG")
      (value "MPT7")
      (footprint "eagle-import:7POL254")
      (libsource (lib "eagle-import") (part "MPT7"))
    )
    (comp (ref "X4")
      (value "MPT8")
      (footprint "eagle-import:8POL254")
      (libsource (lib "eagle-import") (part "MPT8"))
    )
    (comp (ref "X7")
      (value "MPT8")
      (footprint "eagle-import:8POL254")
      (libsource (lib "eagle-import") (part "MPT8"))
    )
    (comp (ref "X8")
      (value "MPT8")
      (footprint "eagle-import:8POL254")
      (libsource (lib "eagle-import") (part "MPT8"))
    )
    (comp (ref "C10")
      (value "0.1UF")
      (footprint "eagle-import:C0805")
      (libsource (lib "eagle-import") (part "C-USC0805"))
    )
    (comp (ref "C11")
      (value "1nF")
      (footprint "eagle-import:C0805")
      (libsource (lib "eagle-import") (part "C-USC0805"))
    )
    (comp (ref "C36")
      (value "1nF")
      (footprint "eagle-import:C0805")
      (libsource (lib "eagle-import") (part "C-USC0805"))
    )
    (comp (ref "C37")
      (value "0.1UF")
      (footprint "eagle-import:C0805")
      (libsource (lib "eagle-import") (part "C-USC0805"))
    )
    (comp (ref "C38")
      (value "1nF")
      (footprint "eagle-import:C0805")
      (libsource (lib "eagle-import") (part "C-USC0805"))
    )
    (comp (ref "C39")
      (value "1nF")
      (footprint "eagle-import:C0805")
      (libsource (lib "eagle-import") (part "C-USC0805"))
    )
    (comp (ref "C40")
      (value "0.1UF")
      (footprint "eagle-import:C0805")
      (libsource (lib "eagle-import") (part "C-USC0805"))
    )
    (comp (ref "C41")
      (value "1nF")
      (footprint "eagle-import:C0805")
      (libsource (lib "eagle-import") (part "C-USC0805"))
    )
    (comp (ref "C42")
      (value "1nF")
      (footprint "eagle-import:C0805")
      (libsource (lib "eagle-import") (part "C-USC0805"))
    )
    (comp (ref "C43")
      (value "0.1UF")
      (footprint "eagle-import:C0805")
      (libsource (lib "eagle-import") (part "C-USC0805"))
    )
    (comp (ref "C44")
      (value "1nF")
      (footprint "eagle-import:C0805")
      (libsource (lib "eagle-import") (part "C-USC0805"))
    )
    (comp (ref "C45")
      (value "1nF")
      (footprint "eagle-import:C0805")
      (libsource (lib "eagle-import") (part "C-USC0805"))
    )
    (comp (ref "C46")
      (value "0.1UF")
      (footprint "eagle-import:C0805")
      (libsource (lib "eagle-import") (part "C-USC0805"))
    )
    (comp (ref "C47")
      (value "?")
      (footprint "eagle-import:C0805")
      (libsource (lib "eagle-import") (part "C-USC0805"))
    )
    (comp (ref "C48")
      (value "?")
      (footprint "eagle-import:C0805")
      (libsource (lib "eagle-import") (part "C-USC0805"))
    )
    (comp (ref "IC13")
      (value "LMV321LICTRT")
      (footprint "eagle-import:SOT23-5")
      (fields (field (name "MF") "ALTERA CORPORATION") (field (name "MPN") "AD8065ARTZ-REEL7"))
      (libsource (lib "eagle-import") (part "LMV321LICTRT"))
    )
    (comp (ref "IC14")
      (value "LMV321LICTRT")
      (footprint "eagle-import:SOT23-5")
      (fields (field (name "MF") "ALTERA CORPORATION") (field (name "MPN") "AD8065ARTZ-REEL7"))
      (libsource (lib "eagle-import") (part "LMV321LICTRT"))
    )
    (comp (ref "IC15")
      (value "LMV321LICTRT")
      (footprint "eagle-import:SOT23-5")
      (fields (field (name "MF") "ALTERA CORPORATION") (field (name "MPN") "AD8065ARTZ-REEL7"))
      (libsource (lib "eagle-import") (part "LMV321LICTRT"))
    )
    (comp (ref "IC16")
      (value "LMV321LICTRT")
      (footprint "eagle-import:SOT23-5")
      (fields (field (name "MF") "ALTERA CORPORATION") (field (name "MPN") "AD8065ARTZ-REEL7"))
      (libsource (lib "eagle-import") (part "LMV321LICTRT"))
    )
    (comp (ref "IC17")
      (value "LMV321LICTRT")
      (footprint "eagle-import:SOT23-5")
      (fields (field (name "MF") "ALTERA CORPORATION") (field (name "MPN") "AD8065ARTZ-REEL7"))
      (libsource (lib "eagle-import") (part "LMV321LICTRT"))
    )
    (comp (ref "LC1")
      (value "PINHD-1X2")
      (footprint "eagle-import:1X02")
      (libsource (lib "eagle-import") (part "PINHD-1X2"))
    )
    (comp (ref "LC2")
      (value "PINHD-1X2")
      (footprint "eagle-import:1X02")
      (libsource (lib "eagle-import") (part "PINHD-1X2"))
    )
    (comp (ref "LC3")
      (value "PINHD-1X2")
      (footprint "eagle-import:1X02")
      (libsource (lib "eagle-import") (part "PINHD-1X2"))
    )
    (comp (ref "LC4")
      (value "PINHD-1X2")
      (footprint "eagle-import:1X02")
      (libsource (lib "eagle-import") (part "PINHD-1X2"))
    )
    (comp (ref "LC5")
      (value "PINHD-1X2")
      (footprint "eagle-import:1X02")
      (libsource (lib "eagle-import") (part "PINHD-1X2"))
    )
    (comp (ref "LCAA_EN")
      (value "PINHD-1X2")
      (footprint "eagle-import:1X02")
      (libsource (lib "eagle-import") (part "PINHD-1X2"))
    )
    (comp (ref "LCIN1")
      (value "PINHD-1X2")
      (footprint "eagle-import:1X02")
      (libsource (lib "eagle-import") (part "PINHD-1X2"))
    )
    (comp (ref "LCIN2")
      (value "PINHD-1X2")
      (footprint "eagle-import:1X02")
      (libsource (lib "eagle-import") (part "PINHD-1X2"))
    )
    (comp (ref "LCIN3")
      (value "PINHD-1X2")
      (footprint "eagle-import:1X02")
      (libsource (lib "eagle-import") (part "PINHD-1X2"))
    )
    (comp (ref "LCIN4")
      (value "PINHD-1X2")
      (footprint "eagle-import:1X02")
      (libsource (lib "eagle-import") (part "PINHD-1X2"))
    )
    (comp (ref "LCIN5")
      (value "PINHD-1X2")
      (footprint "eagle-import:1X02")
      (libsource (lib "eagle-import") (part "PINHD-1X2"))
    )
    (comp (ref "R11")
      (value "24.7K")
      (footprint "eagle-import:R0805")
      (libsource (lib "eagle-import") (part "R-US_R0805"))
    )
    (comp (ref "R12")
      (value "164K")
      (footprint "eagle-import:R0805")
      (libsource (lib "eagle-import") (part "R-US_R0805"))
    )
    (comp (ref "R13")
      (value "50.6K")
      (footprint "eagle-import:R0805")
      (libsource (lib "eagle-import") (part "R-US_R0805"))
    )
    (comp (ref "R14")
      (value "12.6K")
      (footprint "eagle-import:R0805")
      (libsource (lib "eagle-import") (part "R-US_R0805"))
    )
    (comp (ref "R15")
      (value "24.7K")
      (footprint "eagle-import:R0805")
      (libsource (lib "eagle-import") (part "R-US_R0805"))
    )
    (comp (ref "R16")
      (value "164K")
      (footprint "eagle-import:R0805")
      (libsource (lib "eagle-import") (part "R-US_R0805"))
    )
    (comp (ref "R17")
      (value "50.6K")
      (footprint "eagle-import:R0805")
      (libsource (lib "eagle-import") (part "R-US_R0805"))
    )
    (comp (ref "R18")
      (value "12.6K")
      (footprint "eagle-import:R0805")
      (libsource (lib "eagle-import") (part "R-US_R0805"))
    )
    (comp (ref "R19")
      (value "24.7K")
      (footprint "eagle-import:R0805")
      (libsource (lib "eagle-import") (part "R-US_R0805"))
    )
    (comp (ref "R20")
      (value "164K")
      (footprint "eagle-import:R0805")
      (libsource (lib "eagle-import") (part "R-US_R0805"))
    )
    (comp (ref "R21")
      (value "50.6K")
      (footprint "eagle-import:R0805")
      (libsource (lib "eagle-import") (part "R-US_R0805"))
    )
    (comp (ref "R22")
      (value "12.6K")
      (footprint "eagle-import:R0805")
      (libsource (lib "eagle-import") (part "R-US_R0805"))
    )
    (comp (ref "R23")
      (value "24.7K")
      (footprint "eagle-import:R0805")
      (libsource (lib "eagle-import") (part "R-US_R0805"))
    )
    (comp (ref "R24")
      (value "164K")
      (footprint "eagle-import:R0805")
      (libsource (lib "eagle-import") (part "R-US_R0805"))
    )
    (comp (ref "R60")
      (value "50.6K")
      (footprint "eagle-import:R0805")
      (libsource (lib "eagle-import") (part "R-US_R0805"))
    )
    (comp (ref "R61")
      (value "12.6K")
      (footprint "eagle-import:R0805")
      (libsource (lib "eagle-import") (part "R-US_R0805"))
    )
    (comp (ref "R62")
      (value "?")
      (footprint "eagle-import:R0805")
      (libsource (lib "eagle-import") (part "R-US_R0805"))
    )
    (comp (ref "R63")
      (value "?")
      (footprint "eagle-import:R0805")
      (libsource (lib "eagle-import") (part "R-US_R0805"))
    )
    (comp (ref "R64")
      (value "?")
      (footprint "eagle-import:R0805")
      (libsource (lib "eagle-import") (part "R-US_R0805"))
    )
    (comp (ref "R65")
      (value "?")
      (footprint "eagle-import:R0805")
      (libsource (lib "eagle-import") (part "R-US_R0805"))
    )
    (comp (ref "D1")
      (value "1N4004")
      (footprint "eagle-import:DO41-10")
      (libsource (lib "eagle-import") (part "1N4004"))
    )
    (comp (ref "R1")
      (value "10k")
      (footprint "eagle-import:R0805")
      (libsource (lib "eagle-import") (part "R-US_R0805"))
    )
    (comp (ref "R2")
      (value "500k")
      (footprint "eagle-import:R0805")
      (libsource (lib "eagle-import") (part "R-US_R0805"))
    )
    (comp (ref "U$2")
      (value "2N7000")
      (footprint "eagle-import:SOT23")
      (libsource (lib "eagle-import") (part "2N7000"))
    )
    (comp (ref "C8")
      (value "0.1UF")
      (footprint "eagle-import:C0805")
      (libsource (lib "eagle-import") (part "C-USC0805"))
    )
    (comp (ref "C9")
      (value "0.1UF")
      (footprint "eagle-import:C0805")
      (libsource (lib "eagle-import") (part "C-USC0805"))
    )
    (comp (ref "C14")
      (value "0.1UF")
      (footprint "eagle-import:C0805")
      (libsource (lib "eagle-import") (part "C-USC0805"))
    )
    (comp (ref "C15")
      (value "0.1UF")
      (footprint "eagle-import:C0805")
      (libsource (lib "eagle-import") (part "C-USC0805"))
    )
    (comp (ref "IC1")
      (value "LMV321LICTRT")
      (footprint "eagle-import:SOT23-5")
      (fields (field (name "MF") "ALTERA CORPORATION") (field (name "MPN") "AD8065ARTZ-REEL7"))
      (libsource (lib "eagle-import") (part "LMV321LICTRT"))
    )
    (comp (ref "IC2")
      (value "LMV321LICTRT")
      (footprint "eagle-import:SOT23-5")
      (fields (field (name "MF") "ALTERA CORPORATION") (field (name "MPN") "AD8065ARTZ-REEL7"))
      (libsource (lib "eagle-import") (part "LMV321LICTRT"))
    )
    (comp (ref "IC3")
      (value "LMV321LICTRT")
      (footprint "eagle-import:SOT23-5")
      (fields (field (name "MF") "ALTERA CORPORATION") (field (name "MPN") "AD8065ARTZ-REEL7"))
      (libsource (lib "eagle-import") (part "LMV321LICTRT"))
    )
    (comp (ref "IC4")
      (value "LMV321LICTRT")
      (footprint "eagle-import:SOT23-5")
      (fields (field (name "MF") "ALTERA CORPORATION") (field (name "MPN") "AD8065ARTZ-REEL7"))
      (libsource (lib "eagle-import") (part "LMV321LICTRT"))
    )
    (comp (ref "JP2")
      (value "PINHD-1X2")
      (footprint "eagle-import:1X02")
      (libsource (lib "eagle-import") (part "PINHD-1X2"))
    )
    (comp (ref "R31")
      (value "22")
      (footprint "eagle-import:R0805")
      (libsource (lib "eagle-import") (part "R-US_R0805"))
    )
    (comp (ref "R32")
      (value "22")
      (footprint "eagle-import:R0805")
      (libsource (lib "eagle-import") (part "R-US_R0805"))
    )
    (comp (ref "R33")
      (value "22")
      (footprint "eagle-import:R0805")
      (libsource (lib "eagle-import") (part "R-US_R0805"))
    )
    (comp (ref "R34")
      (value "20K")
      (footprint "eagle-import:R0805")
      (libsource (lib "eagle-import") (part "R-US_R0805"))
    )
    (comp (ref "R36")
      (value "20K")
      (footprint "eagle-import:R0805")
      (libsource (lib "eagle-import") (part "R-US_R0805"))
    )
    (comp (ref "R37")
      (value "150K")
      (footprint "eagle-import:R0805")
      (libsource (lib "eagle-import") (part "R-US_R0805"))
    )
    (comp (ref "R38")
      (value "20K")
      (footprint "eagle-import:R0805")
      (libsource (lib "eagle-import") (part "R-US_R0805"))
    )
    (comp (ref "R39")
      (value "3K")
      (footprint "eagle-import:R0805")
      (libsource (lib "eagle-import") (part "R-US_R0805"))
    )
    (comp (ref "R42")
      (value "20K")
      (footprint "eagle-import:R0805")
      (libsource (lib "eagle-import") (part "R-US_R0805"))
    )
    (comp (ref "R43")
      (value "150K")
      (footprint "eagle-import:R0805")
      (libsource (lib "eagle-import") (part "R-US_R0805"))
    )
    (comp (ref "R44")
      (value "20K")
      (footprint "eagle-import:R0805")
      (libsource (lib "eagle-import") (part "R-US_R0805"))
    )
    (comp (ref "R45")
      (value "3K")
      (footprint "eagle-import:R0805")
      (libsource (lib "eagle-import") (part "R-US_R0805"))
    )
    (comp (ref "R52")
      (value "150K")
      (footprint "eagle-import:R0805")
      (libsource (lib "eagle-import") (part "R-US_R0805"))
    )
    (comp (ref "R53")
      (value "20K")
      (footprint "eagle-import:R0805")
      (libsource (lib "eagle-import") (part "R-US_R0805"))
    )
    (comp (ref "R54")
      (value "3K")
      (footprint "eagle-import:R0805")
      (libsource (lib "eagle-import") (part "R-US_R0805"))
    )
    (comp (ref "R55")
      (value "22")
      (footprint "eagle-import:R0805")
      (libsource (lib "eagle-import") (part "R-US_R0805"))
    )
    (comp (ref "R56")
      (value "20K")
      (footprint "eagle-import:R0805")
      (libsource (lib "eagle-import") (part "R-US_R0805"))
    )
    (comp (ref "R57")
      (value "150K")
      (footprint "eagle-import:R0805")
      (libsource (lib "eagle-import") (part "R-US_R0805"))
    )
    (comp (ref "R58")
      (value "20K")
      (footprint "eagle-import:R0805")
      (libsource (lib "eagle-import") (part "R-US_R0805"))
    )
    (comp (ref "R59")
      (value "3K")
      (footprint "eagle-import:R0805")
      (libsource (lib "eagle-import") (part "R-US_R0805"))
    )
    (comp (ref "D2")
      (value "1N4004")
      (footprint "eagle-import:DO41-10")
      (libsource (lib "eagle-import") (part "1N4004"))
    )
    (comp (ref "D3")
      (value "1N4004")
      (footprint "eagle-import:DO41-10")
      (libsource (lib "eagle-import") (part "1N4004"))
    )
    (comp (ref "D4")
      (value "1N4004")
      (footprint "eagle-import:DO41-10")
      (libsource (lib "eagle-import") (part "1N4004"))
    )
    (comp (ref "D6")
      (value "1N4004")
      (footprint "eagle-import:DO41-10")
      (libsource (lib "eagle-import") (part "1N4004"))
    )
    (comp (ref "R3")
      (value "10k")
      (footprint "eagle-import:R0805")
      (libsource (lib "eagle-import") (part "R-US_R0805"))
    )
    (comp (ref "R4")
      (value "500k")
      (footprint "eagle-import:R0805")
      (libsource (lib "eagle-import") (part "R-US_R0805"))
    )
    (comp (ref "R5")
      (value "10k")
      (footprint "eagle-import:R0805")
      (libsource (lib "eagle-import") (part "R-US_R0805"))
    )
    (comp (ref "R6")
      (value "500k")
      (footprint "eagle-import:R0805")
      (libsource (lib "eagle-import") (part "R-US_R0805"))
    )
    (comp (ref "R7")
      (value "10k")
      (footprint "eagle-import:R0805")
      (libsource (lib "eagle-import") (part "R-US_R0805"))
    )
    (comp (ref "R8")
      (value "500k")
      (footprint "eagle-import:R0805")
      (libsource (lib "eagle-import") (part "R-US_R0805"))
    )
    (comp (ref "R9")
      (value "10k")
      (footprint "eagle-import:R0805")
      (libsource (lib "eagle-import") (part "R-US_R0805"))
    )
    (comp (ref "R10")
      (value "500k")
      (footprint "eagle-import:R0805")
      (libsource (lib "eagle-import") (part "R-US_R0805"))
    )
    (comp (ref "U$3")
      (value "2N7000")
      (footprint "eagle-import:SOT23")
      (libsource (lib "eagle-import") (part "2N7000"))
    )
    (comp (ref "U$5")
      (value "IRF740")
      (footprint "eagle-import:TO220BV")
      (libsource (lib "eagle-import") (part "IRF740"))
    )
    (comp (ref "U$8")
      (value "2N7000")
      (footprint "eagle-import:SOT23")
      (libsource (lib "eagle-import") (part "2N7000"))
    )
    (comp (ref "U$9")
      (value "2N7000")
      (footprint "eagle-import:SOT23")
      (libsource (lib "eagle-import") (part "2N7000"))
    )
  )
  (nets
    (net (code "1") (name "+3V3") (class "Default")
      (node (ref "+3.3V_LED") (pin "A") (pinfunction "A_A") (pintype "passive"))
      (node (ref "3.3V_REG") (pin "2") (pinfunction "VOUT_2") (pintype "passive"))
      (node (ref "C4") (pin "+") (pinfunction "+_+") (pintype "passive"))
      (node (ref "JP1") (pin "1") (pinfunction "1_1") (pintype "passive"))
      (node (ref "JP2") (pin "1") (pinfunction "1_1") (pintype "passive"))
      (node (ref "JP4") (pin "1") (pinfunction "1_1") (pintype "passive"))
      (node (ref "PWR_DEBUG") (pin "4") (pinfunction "1_4") (pintype "passive"))
      (node (ref "PWR_OUT2") (pin "A1") (pinfunction "1_A1") (pintype "bidirectional"))
      (node (ref "PWR_OUT2") (pin "B1") (pinfunction "1_B1") (pintype "bidirectional"))
    )
    (net (code "2") (name "+3V3_ADC") (class "Default")
      (node (ref "ADC1") (pin "15") (pinfunction "VREF_15") (pintype "bidirectional"))
      (node (ref "ADC1") (pin "16") (pinfunction "VDD_16") (pintype "bidirectional"))
      (node (ref "ADC2") (pin "15") (pinfunction "VREF_15") (pintype "bidirectional"))
      (node (ref "ADC2") (pin "16") (pinfunction "VDD_16") (pintype "bidirectional"))
      (node (ref "ADC3") (pin "15") (pinfunction "VREF_15") (pintype "bidirectional"))
      (node (ref "ADC3") (pin "16") (pinfunction "VDD_16") (pintype "bidirectional"))
      (node (ref "C1") (pin "1") (pinfunction "1_1") (pintype "passive"))
      (node (ref "C2") (pin "1") (pinfunction "1_1") (pintype "passive"))
      (node (ref "C3") (pin "1") (pinfunction "1_1") (pintype "passive"))
      (node (ref "JP1") (pin "2") (pinfunction "2_2") (pintype "passive"))
      (node (ref "R25") (pin "2") (pinfunction "2_2") (pintype "passive"))
      (node (ref "R29") (pin "2") (pinfunction "2_2") (pintype "passive"))
      (node (ref "R30") (pin "2") (pinfunction "2_2") (pintype "passive"))
    )
    (net (code "3") (name "+3V3_LC") (class "Default")
      (node (ref "C12") (pin "1") (pinfunction "1_1") (pintype "passive"))
      (node (ref "C30") (pin "1") (pinfunction "1_1") (pintype "passive"))
      (node (ref "C32") (pin "1") (pinfunction "1_1") (pintype "passive"))
      (node (ref "C34") (pin "1") (pinfunction "1_1") (pintype "passive"))
      (node (ref "IC10") (pin "7") (pinfunction "+V_7") (pintype "power_in"))
      (node (ref "IC11") (pin "7") (pinfunction "+V_7") (pintype "power_in"))
      (node (ref "IC12") (pin "7") (pinfunction "+V_7") (pintype "power_in"))
      (node (ref "IC5") (pin "7") (pinfunction "+V_7") (pintype "power_in"))
      (node (ref "JP4") (pin "2") (pinfunction "2_2") (pintype "passive"))
      (node (ref "LC_EN/CAL") (pin "1") (pinfunction "1_1") (pintype "passive"))
      (node (ref "RZ1") (pin "E") (pinfunction "E_E") (pintype "passive"))
      (node (ref "RZ2") (pin "E") (pinfunction "E_E") (pintype "passive"))
      (node (ref "RZ3") (pin "E") (pinfunction "E_E") (pintype "passive"))
      (node (ref "RZ4") (pin "E") (pinfunction "E_E") (pintype "passive"))
    )
    (net (code "4") (name "+3V3_PT") (class "Default")
      (node (ref "C14") (pin "1") (pinfunction "1_1") (pintype "passive"))
      (node (ref "C15") (pin "1") (pinfunction "1_1") (pintype "passive"))
      (node (ref "C8") (pin "1") (pinfunction "1_1") (pintype "passive"))
      (node (ref "C9") (pin "1") (pinfunction "1_1") (pintype "passive"))
      (node (ref "IC1") (pin "5") (pinfunction "+VS_5") (pintype "input"))
      (node (ref "IC2") (pin "5") (pinfunction "+VS_5") (pintype "input"))
      (node (ref "IC3") (pin "5") (pinfunction "+VS_5") (pintype "input"))
      (node (ref "IC4") (pin "5") (pinfunction "+VS_5") (pintype "input"))
      (node (ref "JP2") (pin "2") (pinfunction "2_2") (pintype "passive"))
      (node (ref "R38") (pin "1") (pinfunction "1_1") (pintype "passive"))
      (node (ref "R44") (pin "1") (pinfunction "1_1") (pintype "passive"))
      (node (ref "R53") (pin "1") (pinfunction "1_1") (pintype "passive"))
      (node (ref "R58") (pin "1") (pinfunction "1_1") (pintype "passive"))
    )
    (net (code "5") (name "+5V") (class "Default")
      (node (ref "+5V_LED") (pin "A") (pinfunction "A_A") (pintype "passive"))
      (node (ref "3.3V_REG") (pin "3") (pinfunction "VIN_3") (pintype "passive"))
      (node (ref "5V_REG") (pin "2") (pinfunction "VOUT_2") (pintype "input"))
      (node (ref "5V_REG") (pin "4") (pinfunction "4_4") (pintype "passive"))
      (node (ref "C18") (pin "1") (pinfunction "1_1") (pintype "passive"))
      (node (ref "C21") (pin "1") (pinfunction "1_1") (pintype "passive"))
      (node (ref "C24") (pin "1") (pinfunction "1_1") (pintype "passive"))
      (node (ref "C27") (pin "1") (pinfunction "1_1") (pintype "passive"))
      (node (ref "C5") (pin "+") (pinfunction "+_+") (pintype "passive"))
      (node (ref "C7") (pin "+") (pinfunction "+_+") (pintype "passive"))
      (node (ref "IC6") (pin "5") (pinfunction "+VS_5") (pintype "input"))
      (node (ref "IC7") (pin "5") (pinfunction "+VS_5") (pintype "input"))
      (node (ref "IC8") (pin "5") (pinfunction "+VS_5") (pintype "input"))
      (node (ref "IC9") (pin "5") (pinfunction "+VS_5") (pintype "input"))
      (node (ref "LCAA_EN") (pin "1") (pinfunction "1_1") (pintype "passive"))
      (node (ref "PWR_DEBUG") (pin "3") (pinfunction "1_3") (pintype "passive"))
      (node (ref "PWR_OUT2") (pin "A2") (pinfunction "2_A2") (pintype "bidirectional"))
      (node (ref "PWR_OUT2") (pin "B2") (pinfunction "2_B2") (pintype "bidirectional"))
    )
    (net (code "6") (name "+5V_LCAA") (class "Default")
      (node (ref "C10") (pin "1") (pinfunction "1_1") (pintype "passive"))
      (node (ref "C37") (pin "1") (pinfunction "1_1") (pintype "passive"))
      (node (ref "C40") (pin "1") (pinfunction "1_1") (pintype "passive"))
      (node (ref "C43") (pin "1") (pinfunction "1_1") (pintype "passive"))
      (node (ref "C46") (pin "1") (pinfunction "1_1") (pintype "passive"))
      (node (ref "IC13") (pin "5") (pinfunction "+VS_5") (pintype "input"))
      (node (ref "IC14") (pin "5") (pinfunction "+VS_5") (pintype "input"))
      (node (ref "IC15") (pin "5") (pinfunction "+VS_5") (pintype "input"))
      (node (ref "IC16") (pin "5") (pinfunction "+VS_5") (pintype "input"))
      (node (ref "IC17") (pin "5") (pinfunction "+VS_5") (pintype "input"))
      (node (ref "LCAA_EN") (pin "2") (pinfunction "2_2") (pintype "passive"))
    )
    (net (code "7") (name "+5V_RPI") (class "Default")
      (node (ref "RPI_GPIO") (pin "2") (pinfunction "KL_2") (pintype "passive"))
    )
    (net (code "8") (name "+10V") (class "Default")
      (node (ref "10V_REG") (pin "3") (pinfunction "VO_3") (pintype "passive"))
      (node (ref "5V_REG") (pin "3") (pinfunction "VIN_3") (pintype "passive"))
      (node (ref "C16") (pin "+") (pinfunction "+_+") (pintype "passive"))
      (node (ref "C6") (pin "+") (pinfunction "+_+") (pintype "passive"))
      (node (ref "PT1/2") (pin "A1") (pinfunction "1_A1") (pintype "bidirectional"))
      (node (ref "PT1/2") (pin "A3") (pinfunction "3_A3") (pintype "bidirectional"))
      (node (ref "PT1/2") (pin "B1") (pinfunction "1_B1") (pintype "bidirectional"))
      (node (ref "PT1/2") (pin "B3") (pinfunction "3_B3") (pintype "bidirectional"))
      (node (ref "PT3/4") (pin "A1") (pinfunction "1_A1") (pintype "bidirectional"))
      (node (ref "PT3/4") (pin "A3") (pinfunction "3_A3") (pintype "bidirectional"))
      (node (ref "PT3/4") (pin "B1") (pinfunction "1_B1") (pintype "bidirectional"))
      (node (ref "PT3/4") (pin "B3") (pinfunction "3_B3") (pintype "bidirectional"))
      (node (ref "PWR_DEBUG") (pin "2") (pinfunction "1_2") (pintype "passive"))
      (node (ref "PWR_OUT1") (pin "A1") (pinfunction "1_A1") (pintype "bidirectional"))
      (node (ref "PWR_OUT1") (pin "B1") (pinfunction "1_B1") (pintype "bidirectional"))
      (node (ref "R35") (pin "2") (pinfunction "2_2") (pintype "passive"))
    )
    (net (code "9") (name "+12V") (class "Default")
      (node (ref "+12V_LED") (pin "A") (pinfunction "A_A") (pintype "passive"))
      (node (ref "10V_REG") (pin "1") (pinfunction "VI_1") (pintype "input"))
      (node (ref "C17") (pin "+") (pinfunction "+_+") (pintype "passive"))
      (node (ref "D1") (pin "C") (pinfunction "C_C") (pintype "passive"))
      (node (ref "D2") (pin "C") (pinfunction "C_C") (pintype "passive"))
      (node (ref "D3") (pin "C") (pinfunction "C_C") (pintype "passive"))
      (node (ref "D4") (pin "C") (pinfunction "C_C") (pintype "passive"))
      (node (ref "D5") (pin "C") (pinfunction "C_C") (pintype "passive"))
      (node (ref "D6") (pin "C") (pinfunction "C_C") (pintype "passive"))
      (node (ref "PWR_DEBUG") (pin "1") (pinfunction "1_1") (pintype "passive"))
      (node (ref "PWR_OUT1") (pin "A2") (pinfunction "2_A2") (pintype "bidirectional"))
      (node (ref "PWR_OUT1") (pin "B2") (pinfunction "2_B2") (pintype "bidirectional"))
    )
    (net (code "10") (name "+12V_DEBUG") (class "Default")
      (node (ref "PWR_IN") (pin "A1") (pinfunction "1_A1") (pintype "bidirectional"))
      (node (ref "PWR_IN") (pin "B1") (pinfunction "1_B1") (pintype "bidirectional"))
      (node (ref "U6") (pin "2") (pinfunction "P_2") (pintype "passive"))
    )
    (net (code "17") (name "ADC1_A0") (class "Default")
      (node (ref "ADC1") (pin "1") (pinfunction "CH0_1") (pintype "bidirectional"))
      (node (ref "LC1") (pin "1") (pinfunction "1_1") (pintype "passive"))
      (node (ref "X4") (pin "1") (pinfunction "1_1") (pintype "passive"))
    )
    (net (code "18") (name "ADC1_A1") (class "Default")
      (node (ref "ADC1") (pin "2") (pinfunction "CH1_2") (pintype "bidirectional"))
      (node (ref "LC2") (pin "1") (pinfunction "1_1") (pintype "passive"))
      (node (ref "X4") (pin "2") (pinfunction "1_2") (pintype "passive"))
    )
    (net (code "19") (name "ADC1_A2") (class "Default")
      (node (ref "ADC1") (pin "3") (pinfunction "CH2_3") (pintype "bidirectional"))
      (node (ref "X4") (pin "3") (pinfunction "1_3") (pintype "passive"))
    )
    (net (code "20") (name "ADC1_A3") (class "Default")
      (node (ref "ADC1") (pin "4") (pinfunction "CH3_4") (pintype "bidirectional"))
      (node (ref "LC3") (pin "1") (pinfunction "1_1") (pintype "passive"))
      (node (ref "X4") (pin "4") (pinfunction "1_4") (pintype "passive"))
    )
    (net (code "21") (name "ADC1_A4") (class "Default")
      (node (ref "ADC1") (pin "5") (pinfunction "CH4_5") (pintype "bidirectional"))
      (node (ref "LC4") (pin "1") (pinfunction "1_1") (pintype "passive"))
      (node (ref "X4") (pin "5") (pinfunction "1_5") (pintype "passive"))
    )
    (net (code "22") (name "ADC1_A5") (class "Default")
      (node (ref "ADC1") (pin "6") (pinfunction "CH5_6") (pintype "bidirectional"))
      (node (ref "LC5") (pin "1") (pinfunction "1_1") (pintype "passive"))
      (node (ref "X4") (pin "6") (pinfunction "1_6") (pintype "passive"))
    )
    (net (code "23") (name "ADC1_A6") (class "Default")
      (node (ref "ADC1") (pin "7") (pinfunction "CH6_7") (pintype "bidirectional"))
      (node (ref "X4") (pin "7") (pinfunction "1_7") (pintype "passive"))
    )
    (net (code "24") (name "ADC1_A7") (class "Default")
      (node (ref "ADC1") (pin "8") (pinfunction "CH7_8") (pintype "bidirectional"))
      (node (ref "X4") (pin "8") (pinfunction "1_8") (pintype "passive"))
    )
    (net (code "25") (name "ADC1_CS") (class "Default")
      (node (ref "ADC1") (pin "10") (pinfunction "CS*_10") (pintype "bidirectional"))
      (node (ref "R25") (pin "1") (pinfunction "1_1") (pintype "passive"))
      (node (ref "RPI_DEBUG") (pin "4") (pinfunction "1_4") (pintype "passive"))
      (node (ref "RPI_GPIO") (pin "22") (pinfunction "KL_22") (pintype "passive"))
    )
    (net (code "26") (name "ADC2_A0") (class "Default")
      (node (ref "ADC2") (pin "1") (pinfunction "CH0_1") (pintype "bidirectional"))
      (node (ref "IC6") (pin "3") (pinfunction "IN-_3") (pintype "input"))
      (node (ref "IC6") (pin "4") (pinfunction "OUT_4") (pintype "output"))
      (node (ref "X7") (pin "1") (pinfunction "1_1") (pintype "passive"))
    )
    (net (code "27") (name "ADC2_A1") (class "Default")
      (node (ref "ADC2") (pin "2") (pinfunction "CH1_2") (pintype "bidirectional"))
      (node (ref "IC7") (pin "3") (pinfunction "IN-_3") (pintype "input"))
      (node (ref "IC7") (pin "4") (pinfunction "OUT_4") (pintype "output"))
      (node (ref "X7") (pin "2") (pinfunction "1_2") (pintype "passive"))
    )
    (net (code "28") (name "ADC2_A2") (class "Default")
      (node (ref "ADC2") (pin "3") (pinfunction "CH2_3") (pintype "bidirectional"))
      (node (ref "IC8") (pin "3") (pinfunction "IN-_3") (pintype "input"))
      (node (ref "IC8") (pin "4") (pinfunction "OUT_4") (pintype "output"))
      (node (ref "X7") (pin "3") (pinfunction "1_3") (pintype "passive"))
    )
    (net (code "29") (name "ADC2_A3") (class "Default")
      (node (ref "ADC2") (pin "4") (pinfunction "CH3_4") (pintype "bidirectional"))
      (node (ref "IC9") (pin "3") (pinfunction "IN-_3") (pintype "input"))
      (node (ref "IC9") (pin "4") (pinfunction "OUT_4") (pintype "output"))
      (node (ref "X7") (pin "4") (pinfunction "1_4") (pintype "passive"))
    )
    (net (code "30") (name "ADC2_A4") (class "Default")
      (node (ref "ADC2") (pin "5") (pinfunction "CH4_5") (pintype "bidirectional"))
      (node (ref "THERMOCOUPLES") (pin "A1") (pinfunction "1_A1") (pintype "bidirectional"))
      (node (ref "THERMOCOUPLES") (pin "B1") (pinfunction "1_B1") (pintype "bidirectional"))
      (node (ref "X7") (pin "5") (pinfunction "1_5") (pintype "passive"))
    )
    (net (code "31") (name "ADC2_A5") (class "Default")
      (node (ref "ADC2") (pin "6") (pinfunction "CH5_6") (pintype "bidirectional"))
      (node (ref "THERMOCOUPLES") (pin "A2") (pinfunction "2_A2") (pintype "bidirectional"))
      (node (ref "THERMOCOUPLES") (pin "B2") (pinfunction "2_B2") (pintype "bidirectional"))
      (node (ref "X7") (pin "6") (pinfunction "1_6") (pintype "passive"))
    )
    (net (code "32") (name "ADC2_A6") (class "Default")
      (node (ref "ADC2") (pin "7") (pinfunction "CH6_7") (pintype "bidirectional"))
      (node (ref "THERMOCOUPLES") (pin "A3") (pinfunction "3_A3") (pintype "bidirectional"))
      (node (ref "THERMOCOUPLES") (pin "B3") (pinfunction "3_B3") (pintype "bidirectional"))
      (node (ref "X7") (pin "7") (pinfunction "1_7") (pintype "passive"))
    )
    (net (code "33") (name "ADC2_A7") (class "Default")
      (node (ref "ADC2") (pin "8") (pinfunction "CH7_8") (pintype "bidirectional"))
      (node (ref "THERMOCOUPLES") (pin "A4") (pinfunction "4_A4") (pintype "bidirectional"))
      (node (ref "THERMOCOUPLES") (pin "B4") (pinfunction "4_B4") (pintype "bidirectional"))
      (node (ref "X7") (pin "8") (pinfunction "1_8") (pintype "passive"))
    )
    (net (code "34") (name "ADC2_CS") (class "Default")
      (node (ref "ADC2") (pin "10") (pinfunction "CS*_10") (pintype "bidirectional"))
      (node (ref "R29") (pin "1") (pinfunction "1_1") (pintype "passive"))
      (node (ref "RPI_DEBUG") (pin "3") (pinfunction "1_3") (pintype "passive"))
      (node (ref "RPI_GPIO") (pin "24") (pinfunction "KL_24") (pintype "passive"))
    )
    (net (code "35") (name "ADC3_A0") (class "Default")
      (node (ref "ADC3") (pin "1") (pinfunction "CH0_1") (pintype "bidirectional"))
      (node (ref "X8") (pin "1") (pinfunction "1_1") (pintype "passive"))
    )
    (net (code "36") (name "ADC3_A1") (class "Default")
      (node (ref "ADC3") (pin "2") (pinfunction "CH1_2") (pintype "bidirectional"))
      (node (ref "X8") (pin "2") (pinfunction "1_2") (pintype "passive"))
    )
    (net (code "37") (name "ADC3_A2") (class "Default")
      (node (ref "ADC3") (pin "3") (pinfunction "CH2_3") (pintype "bidirectional"))
      (node (ref "X8") (pin "3") (pinfunction "1_3") (pintype "passive"))
    )
    (net (code "38") (name "ADC3_A3") (class "Default")
      (node (ref "ADC3") (pin "4") (pinfunction "CH3_4") (pintype "bidirectional"))
      (node (ref "X8") (pin "4") (pinfunction "1_4") (pintype "passive"))
    )
    (net (code "39") (name "ADC3_A4") (class "Default")
      (node (ref "ADC3") (pin "5") (pinfunction "CH4_5") (pintype "bidirectional"))
      (node (ref "X8") (pin "5") (pinfunction "1_5") (pintype "passive"))
    )
    (net (code "40") (name "ADC3_A5") (class "Default")
      (node (ref "ADC3") (pin "6") (pinfunction "CH5_6") (pintype "bidirectional"))
      (node (ref "X8") (pin "6") (pinfunction "1_6") (pintype "passive"))
    )
    (net (code "41") (name "ADC3_A6") (class "Default")
      (node (ref "ADC3") (pin "7") (pinfunction "CH6_7") (pintype "bidirectional"))
      (node (ref "X8") (pin "7") (pinfunction "1_7") (pintype "passive"))
    )
    (net (code "42") (name "ADC3_A7") (class "Default")
      (node (ref "ADC3") (pin "8") (pinfunction "CH7_8") (pintype "bidirectional"))
      (node (ref "X8") (pin "8") (pinfunction "1_8") (pintype "passive"))
    )
    (net (code "43") (name "ADC3_CS") (class "Default")
      (node (ref "ADC3") (pin "10") (pinfunction "CS*_10") (pintype "bidirectional"))
      (node (ref "R30") (pin "1") (pinfunction "1_1") (pintype "passive"))
      (node (ref "RPI_DEBUG") (pin "2") (pinfunction "1_2") (pintype "passive"))
      (node (ref "RPI_GPIO") (pin "26") (pinfunction "KL_26") (pintype "passive"))
    )
    (net (code "44") (name "CAL") (class "Default")
      (node (ref "IC10") (pin "8") (pinfunction "ENCAL_8") (pintype "input"))
      (node (ref "IC11") (pin "8") (pinfunction "ENCAL_8") (pintype "input"))
      (node (ref "IC12") (pin "8") (pinfunction "ENCAL_8") (pintype "input"))
      (node (ref "IC5") (pin "8") (pinfunction "ENCAL_8") (pintype "input"))
      (node (ref "LC_EN/CAL") (pin "2") (pinfunction "2_2") (pintype "passive"))
      (node (ref "RPD1") (pin "1") (pinfunction "1_1") (pintype "passive"))
    )
    (net (code "45") (name "CTRL_SOLENOID_1") (class "Default")
      (node (ref "R3") (pin "1") (pinfunction "1_1") (pintype "passive"))
      (node (ref "RPI_GPIO") (pin "11") (pinfunction "KL_11") (pintype "passive"))
    )
    (net (code "46") (name "CTRL_SOLENOID_2") (class "Default")
      (node (ref "R5") (pin "1") (pinfunction "1_1") (pintype "passive"))
      (node (ref "RPI_GPIO") (pin "13") (pinfunction "KL_13") (pintype "passive"))
    )
    (net (code "47") (name "CTRL_SOLENOID_3") (class "Default")
      (node (ref "R7") (pin "1") (pinfunction "1_1") (pintype "passive"))
      (node (ref "RPI_GPIO") (pin "15") (pinfunction "KL_15") (pintype "passive"))
    )
    (net (code "48") (name "CTRL_SOLENOID_4") (class "Default")
      (node (ref "R9") (pin "1") (pinfunction "1_1") (pintype "passive"))
      (node (ref "RPI_GPIO") (pin "18") (pinfunction "KL_18") (pintype "passive"))
    )
    (net (code "49") (name "GND") (class "Default")
      (node (ref "+10V_LED") (pin "K") (pinfunction "C_K") (pintype "passive"))
      (node (ref "10V_REG") (pin "2") (pinfunction "GND_2") (pintype "passive"))
      (node (ref "3.3V_REG") (pin "1") (pinfunction "GND_1") (pintype "passive"))
      (node (ref "5V_REG") (pin "1") (pinfunction "GND_1") (pintype "output"))
      (node (ref "ADC1") (pin "14") (pinfunction "AGND_14") (pintype "bidirectional"))
      (node (ref "ADC1") (pin "9") (pinfunction "DGND_9") (pintype "bidirectional"))
      (node (ref "ADC2") (pin "14") (pinfunction "AGND_14") (pintype "bidirectional"))
      (node (ref "ADC2") (pin "9") (pinfunction "DGND_9") (pintype "bidirectional"))
      (node (ref "ADC3") (pin "14") (pinfunction "AGND_14") (pintype "bidirectional"))
      (node (ref "ADC3") (pin "9") (pinfunction "DGND_9") (pintype "bidirectional"))
      (node (ref "C1") (pin "2") (pinfunction "2_2") (pintype "passive"))
      (node (ref "C10") (pin "2") (pinfunction "2_2") (pintype "passive"))
      (node (ref "C12") (pin "2") (pinfunction "2_2") (pintype "passive"))
      (node (ref "C14") (pin "2") (pinfunction "2_2") (pintype "passive"))
      (node (ref "C15") (pin "2") (pinfunction "2_2") (pintype "passive"))
      (node (ref "C16") (pin "-") (pinfunction "-_-") (pintype "passive"))
      (node (ref "C17") (pin "-") (pinfunction "-_-") (pintype "passive"))
      (node (ref "C18") (pin "2") (pinfunction "2_2") (pintype "passive"))
      (node (ref "C19") (pin "2") (pinfunction "2_2") (pintype "passive"))
      (node (ref "C2") (pin "2") (pinfunction "2_2") (pintype "passive"))
      (node (ref "C20") (pin "2") (pinfunction "2_2") (pintype "passive"))
      (node (ref "C21") (pin "2") (pinfunction "2_2") (pintype "passive"))
      (node (ref "C22") (pin "2") (pinfunction "2_2") (pintype "passive"))
      (node (ref "C23") (pin "2") (pinfunction "2_2") (pintype "passive"))
      (node (ref "C24") (pin "2") (pinfunction "2_2") (pintype "passive"))
      (node (ref "C25") (pin "2") (pinfunction "2_2") (pintype "passive"))
      (node (ref "C26") (pin "2") (pinfunction "2_2") (pintype "passive"))
      (node (ref "C27") (pin "2") (pinfunction "2_2") (pintype "passive"))
      (node (ref "C28") (pin "2") (pinfunction "2_2") (pintype "passive"))
      (node (ref "C29") (pin "2") (pinfunction "2_2") (pintype "passive"))
      (node (ref "C3") (pin "2") (pinfunction "2_2") (pintype "passive"))
      (node (ref "C30") (pin "2") (pinfunction "2_2") (pintype "passive"))
      (node (ref "C32") (pin "2") (pinfunction "2_2") (pintype "passive"))
      (node (ref "C34") (pin "2") (pinfunction "2_2") (pintype "passive"))
      (node (ref "C36") (pin "2") (pinfunction "2_2") (pintype "passive"))
      (node (ref "C37") (pin "2") (pinfunction "2_2") (pintype "passive"))
      (node (ref "C38") (pin "2") (pinfunction "2_2") (pintype "passive"))
      (node (ref "C4") (pin "-") (pinfunction "-_-") (pintype "passive"))
      (node (ref "C40") (pin "2") (pinfunction "2_2") (pintype "passive"))
      (node (ref "C41") (pin "2") (pinfunction "2_2") (pintype "passive"))
      (node (ref "C43") (pin "2") (pinfunction "2_2") (pintype "passive"))
      (node (ref "C44") (pin "2") (pinfunction "2_2") (pintype "passive"))
      (node (ref "C46") (pin "2") (pinfunction "2_2") (pintype "passive"))
      (node (ref "C47") (pin "2") (pinfunction "2_2") (pintype "passive"))
      (node (ref "C5") (pin "-") (pinfunction "-_-") (pintype "passive"))
      (node (ref "C6") (pin "-") (pinfunction "-_-") (pintype "passive"))
      (node (ref "C7") (pin "-") (pinfunction "-_-") (pintype "passive"))
      (node (ref "C8") (pin "2") (pinfunction "2_2") (pintype "passive"))
      (node (ref "C9") (pin "2") (pinfunction "2_2") (pintype "passive"))
      (node (ref "IC1") (pin "2") (pinfunction "-VS_2") (pintype "input"))
      (node (ref "IC10") (pin "4") (pinfunction "-V_4") (pintype "power_in"))
      (node (ref "IC11") (pin "4") (pinfunction "-V_4") (pintype "power_in"))
      (node (ref "IC12") (pin "4") (pinfunction "-V_4") (pintype "power_in"))
      (node (ref "IC13") (pin "2") (pinfunction "-VS_2") (pintype "input"))
      (node (ref "IC14") (pin "2") (pinfunction "-VS_2") (pintype "input"))
      (node (ref "IC15") (pin "2") (pinfunction "-VS_2") (pintype "input"))
      (node (ref "IC16") (pin "2") (pinfunction "-VS_2") (pintype "input"))
      (node (ref "IC17") (pin "2") (pinfunction "-VS_2") (pintype "input"))
      (node (ref "IC2") (pin "2") (pinfunction "-VS_2") (pintype "input"))
      (node (ref "IC3") (pin "2") (pinfunction "-VS_2") (pintype "input"))
      (node (ref "IC4") (pin "2") (pinfunction "-VS_2") (pintype "input"))
      (node (ref "IC5") (pin "4") (pinfunction "-V_4") (pintype "power_in"))
      (node (ref "IC6") (pin "2") (pinfunction "-VS_2") (pintype "input"))
      (node (ref "IC7") (pin "2") (pinfunction "-VS_2") (pintype "input"))
      (node (ref "IC8") (pin "2") (pinfunction "-VS_2") (pintype "input"))
      (node (ref "IC9") (pin "2") (pinfunction "-VS_2") (pintype "input"))
      (node (ref "PWR_DEBUG") (pin "5") (pinfunction "1_5") (pintype "passive"))
      (node (ref "PWR_IN") (pin "A2") (pinfunction "2_A2") (pintype "bidirectional"))
      (node (ref "PWR_IN") (pin "B2") (pinfunction "2_B2") (pintype "bidirectional"))
      (node (ref "R10") (pin "2") (pinfunction "2_2") (pintype "passive"))
      (node (ref "R14") (pin "2") (pinfunction "2_2") (pintype "passive"))
      (node (ref "R18") (pin "2") (pinfunction "2_2") (pintype "passive"))
      (node (ref "R2") (pin "2") (pinfunction "2_2") (pintype "passive"))
      (node (ref "R22") (pin "2") (pinfunction "2_2") (pintype "passive"))
      (node (ref "R26") (pin "1") (pinfunction "1_1") (pintype "passive"))
      (node (ref "R27") (pin "2") (pinfunction "2_2") (pintype "passive"))
      (node (ref "R28") (pin "2") (pinfunction "2_2") (pintype "passive"))
      (node (ref "R31") (pin "1") (pinfunction "1_1") (pintype "passive"))
      (node (ref "R32") (pin "1") (pinfunction "1_1") (pintype "passive"))
      (node (ref "R33") (pin "1") (pinfunction "1_1") (pintype "passive"))
      (node (ref "R39") (pin "2") (pinfunction "2_2") (pintype "passive"))
      (node (ref "R4") (pin "2") (pinfunction "2_2") (pintype "passive"))
      (node (ref "R45") (pin "2") (pinfunction "2_2") (pintype "passive"))
      (node (ref "R54") (pin "2") (pinfunction "2_2") (pintype "passive"))
      (node (ref "R55") (pin "1") (pinfunction "1_1") (pintype "passive"))
      (node (ref "R59") (pin "2") (pinfunction "2_2") (pintype "passive"))
      (node (ref "R6") (pin "2") (pinfunction "2_2") (pintype "passive"))
      (node (ref "R61") (pin "2") (pinfunction "2_2") (pintype "passive"))
      (node (ref "R65") (pin "2") (pinfunction "2_2") (pintype "passive"))
      (node (ref "R8") (pin "2") (pinfunction "2_2") (pintype "passive"))
      (node (ref "RPD1") (pin "2") (pinfunction "2_2") (pintype "passive"))
      (node (ref "RPI_DEBUG") (pin "1") (pinfunction "1_1") (pintype "passive"))
      (node (ref "RPI_GPIO") (pin "6") (pinfunction "KL_6") (pintype "passive"))
      (node (ref "RZ1") (pin "A") (pinfunction "A_A") (pintype "passive"))
      (node (ref "RZ2") (pin "A") (pinfunction "A_A") (pintype "passive"))
      (node (ref "RZ3") (pin "A") (pinfunction "A_A") (pintype "passive"))
      (node (ref "RZ4") (pin "A") (pinfunction "A_A") (pintype "passive"))
      (node (ref "U$2") (pin "2") (pinfunction "S_2") (pintype "passive"))
      (node (ref "U$3") (pin "2") (pinfunction "S_2") (pintype "passive"))
      (node (ref "U$5") (pin "S") (pinfunction "S_S") (pintype "passive"))
      (node (ref "U$8") (pin "2") (pinfunction "S_2") (pintype "passive"))
      (node (ref "U$9") (pin "2") (pinfunction "S_2") (pintype "passive"))
    )
    (net (code "50") (name "IGNITION_RELAY") (class "Default")
      (node (ref "R1") (pin "1") (pinfunction "1_1") (pintype "passive"))
      (node (ref "RPI_GPIO") (pin "16") (pinfunction "KL_16") (pintype "passive"))
    )
    (net (code "51") (name "LC1_PREC") (class "Default")
      (node (ref "IC5") (pin "6") (pinfunction "OUT_6") (pintype "output"))
      (node (ref "LCIN1") (pin "2") (pinfunction "2_2") (pintype "passive"))
      (node (ref "RF1") (pin "1") (pinfunction "1_1") (pintype "passive"))
    )
    (net (code "52") (name "LC2_PREC") (class "Default")
      (node (ref "IC10") (pin "6") (pinfunction "OUT_6") (pintype "output"))
      (node (ref "LCIN2") (pin "2") (pinfunction "2_2") (pintype "passive"))
      (node (ref "RF2") (pin "1") (pinfunction "1_1") (pintype "passive"))
    )
    (net (code "53") (name "LC3_PREC") (class "Default")
      (node (ref "IC11") (pin "6") (pinfunction "OUT_6") (pintype "output"))
      (node (ref "LCIN3") (pin "2") (pinfunction "2_2") (pintype "passive"))
      (node (ref "RF3") (pin "1") (pinfunction "1_1") (pintype "passive"))
    )
    (net (code "54") (name "LC4_PREC") (class "Default")
      (node (ref "IC12") (pin "6") (pinfunction "OUT_6") (pintype "output"))
      (node (ref "LCIN4") (pin "2") (pinfunction "2_2") (pintype "passive"))
      (node (ref "RF4") (pin "1") (pinfunction "1_1") (pintype "passive"))
    )
    (net (code "55") (name "LC_1_OUT+") (class "Default")
      (node (ref "IC5") (pin "3") (pinfunction "+_3") (pintype "input"))
      (node (ref "LC1/2") (pin "A3") (pinfunction "3_A3") (pintype "bidirectional"))
      (node (ref "LC1/2") (pin "B3") (pinfunction "3_B3") (pintype "bidirectional"))
    )
    (net (code "56") (name "LC_1_OUT-") (class "Default")
      (node (ref "IC5") (pin "2") (pinfunction "-_2") (pintype "input"))
      (node (ref "LC1/2") (pin "A4") (pinfunction "4_A4") (pintype "bidirectional"))
      (node (ref "LC1/2") (pin "B4") (pinfunction "4_B4") (pintype "bidirectional"))
    )
    (net (code "57") (name "LC_2_OUT+") (class "Default")
      (node (ref "IC10") (pin "3") (pinfunction "+_3") (pintype "input"))
      (node (ref "LC1/2") (pin "A1") (pinfunction "1_A1") (pintype "bidirectional"))
      (node (ref "LC1/2") (pin "B1") (pinfunction "1_B1") (pintype "bidirectional"))
    )
    (net (code "58") (name "LC_2_OUT-") (class "Default")
      (node (ref "IC10") (pin "2") (pinfunction "-_2") (pintype "input"))
      (node (ref "LC1/2") (pin "A2") (pinfunction "2_A2") (pintype "bidirectional"))
      (node (ref "LC1/2") (pin "B2") (pinfunction "2_B2") (pintype "bidirectional"))
    )
    (net (code "59") (name "LC_3_OUT+") (class "Default")
      (node (ref "IC11") (pin "3") (pinfunction "+_3") (pintype "input"))
      (node (ref "LC3/4") (pin "A3") (pinfunction "3_A3") (pintype "bidirectional"))
      (node (ref "LC3/4") (pin "B3") (pinfunction "3_B3") (pintype "bidirectional"))
    )
    (net (code "60") (name "LC_3_OUT-") (class "Default")
      (node (ref "IC11") (pin "2") (pinfunction "-_2") (pintype "input"))
      (node (ref "LC3/4") (pin "A4") (pinfunction "4_A4") (pintype "bidirectional"))
      (node (ref "LC3/4") (pin "B4") (pinfunction "4_B4") (pintype "bidirectional"))
    )
    (net (code "61") (name "LC_4_OUT+") (class "Default")
      (node (ref "IC12") (pin "3") (pinfunction "+_3") (pintype "input"))
      (node (ref "LC3/4") (pin "A1") (pinfunction "1_A1") (pintype "bidirectional"))
      (node (ref "LC3/4") (pin "B1") (pinfunction "1_B1") (pintype "bidirectional"))
    )
    (net (code "62") (name "LC_4_OUT-") (class "Default")
      (node (ref "IC12") (pin "2") (pinfunction "-_2") (pintype "input"))
      (node (ref "LC3/4") (pin "A2") (pinfunction "2_A2") (pintype "bidirectional"))
      (node (ref "LC3/4") (pin "B2") (pinfunction "2_B2") (pintype "bidirectional"))
    )
    (net (code "63") (name "MISO") (class "Default")
      (node (ref "ADC1") (pin "12") (pinfunction "DOUT_12") (pintype "bidirectional"))
      (node (ref "ADC2") (pin "12") (pinfunction "DOUT_12") (pintype "bidirectional"))
      (node (ref "ADC3") (pin "12") (pinfunction "DOUT_12") (pintype "bidirectional"))
      (node (ref "RPI_DEBUG") (pin "6") (pinfunction "1_6") (pintype "passive"))
      (node (ref "RPI_GPIO") (pin "21") (pinfunction "KL_21") (pintype "passive"))
    )
    (net (code "64") (name "MOSI") (class "Default")
      (node (ref "ADC1") (pin "11") (pinfunction "DIN_11") (pintype "bidirectional"))
      (node (ref "ADC2") (pin "11") (pinfunction "DIN_11") (pintype "bidirectional"))
      (node (ref "ADC3") (pin "11") (pinfunction "DIN_11") (pintype "bidirectional"))
      (node (ref "RPI_DEBUG") (pin "5") (pinfunction "1_5") (pintype "passive"))
      (node (ref "RPI_GPIO") (pin "19") (pinfunction "KL_19") (pintype "passive"))
    )
    (net (code "65") (name "Net-(+3.3V_LED-C)") (class "Default")
      (node (ref "+3.3V_LED") (pin "K") (pinfunction "C_K") (pintype "passive"))
      (node (ref "R28") (pin "1") (pinfunction "1_1") (pintype "passive"))
    )
    (net (code "66") (name "Net-(+5V_LED-C)") (class "Default")
      (node (ref "+5V_LED") (pin "K") (pinfunction "C_K") (pintype "passive"))
      (node (ref "R27") (pin "1") (pinfunction "1_1") (pintype "passive"))
    )
    (net (code "67") (name "Net-(+10V_LED-PadA)") (class "Default")
      (node (ref "+10V_LED") (pin "A") (pinfunction "A_A") (pintype "passive"))
      (node (ref "R35") (pin "1") (pinfunction "1_1") (pintype "passive"))
    )
    (net (code "68") (name "Net-(+12V_LED-C)") (class "Default")
      (node (ref "+12V_LED") (pin "K") (pinfunction "C_K") (pintype "passive"))
      (node (ref "R26") (pin "2") (pinfunction "2_2") (pintype "passive"))
    )
    (net (code "69") (name "Net-(C11-Pad1)") (class "Default")
      (node (ref "C11") (pin "1") (pinfunction "1_1") (pintype "passive"))
      (node (ref "R11") (pin "1") (pinfunction "1_1") (pintype "passive"))
      (node (ref "R12") (pin "2") (pinfunction "2_2") (pintype "passive"))
    )
    (net (code "70") (name "Net-(C19-Pad1)") (class "Default")
      (node (ref "C19") (pin "1") (pinfunction "1_1") (pintype "passive"))
      (node (ref "R40") (pin "2") (pinfunction "2_2") (pintype "passive"))
      (node (ref "R41") (pin "1") (pinfunction "1_1") (pintype "passive"))
    )
    (net (code "71") (name "Net-(C22-Pad1)") (class "Default")
      (node (ref "C22") (pin "1") (pinfunction "1_1") (pintype "passive"))
      (node (ref "R46") (pin "1") (pinfunction "1_1") (pintype "passive"))
      (node (ref "R47") (pin "2") (pinfunction "2_2") (pintype "passive"))
    )
    (net (code "72") (name "Net-(C25-Pad1)") (class "Default")
      (node (ref "C25") (pin "1") (pinfunction "1_1") (pintype "passive"))
      (node (ref "R48") (pin "1") (pinfunction "1_1") (pintype "passive"))
      (node (ref "R49") (pin "2") (pinfunction "2_2") (pintype "passive"))
    )
    (net (code "73") (name "Net-(C28-Pad1)") (class "Default")
      (node (ref "C28") (pin "1") (pinfunction "1_1") (pintype "passive"))
      (node (ref "R50") (pin "1") (pinfunction "1_1") (pintype "passive"))
      (node (ref "R51") (pin "2") (pinfunction "2_2") (pintype "passive"))
    )
    (net (code "74") (name "Net-(C39-Pad1)") (class "Default")
      (node (ref "C39") (pin "1") (pinfunction "1_1") (pintype "passive"))
      (node (ref "R15") (pin "1") (pinfunction "1_1") (pintype "passive"))
      (node (ref "R16") (pin "2") (pinfunction "2_2") (pintype "passive"))
    )
    (net (code "75") (name "Net-(C42-Pad1)") (class "Default")
      (node (ref "C42") (pin "1") (pinfunction "1_1") (pintype "passive"))
      (node (ref "R19") (pin "1") (pinfunction "1_1") (pintype "passive"))
      (node (ref "R20") (pin "2") (pinfunction "2_2") (pintype "passive"))
    )
    (net (code "76") (name "Net-(C45-Pad1)") (class "Default")
      (node (ref "C45") (pin "1") (pinfunction "1_1") (pintype "passive"))
      (node (ref "R23") (pin "1") (pinfunction "1_1") (pintype "passive"))
      (node (ref "R24") (pin "2") (pinfunction "2_2") (pintype "passive"))
    )
    (net (code "77") (name "Net-(C48-Pad1)") (class "Default")
      (node (ref "C48") (pin "1") (pinfunction "1_1") (pintype "passive"))
      (node (ref "R62") (pin "1") (pinfunction "1_1") (pintype "passive"))
      (node (ref "R63") (pin "2") (pinfunction "2_2") (pintype "passive"))
    )
    (net (code "78") (name "Net-(IC1-IN+)") (class "Default")
      (node (ref "IC1") (pin "1") (pinfunction "IN+_1") (pintype "input"))
      (node (ref "R38") (pin "2") (pinfunction "2_2") (pintype "passive"))
      (node (ref "R39") (pin "1") (pinfunction "1_1") (pintype "passive"))
    )
    (net (code "79") (name "Net-(IC1-IN-)") (class "Default")
      (node (ref "IC1") (pin "3") (pinfunction "IN-_3") (pintype "input"))
      (node (ref "R36") (pin "1") (pinfunction "1_1") (pintype "passive"))
      (node (ref "R37") (pin "2") (pinfunction "2_2") (pintype "passive"))
    )
    (net (code "80") (name "Net-(IC2-IN+)") (class "Default")
      (node (ref "IC2") (pin "1") (pinfunction "IN+_1") (pintype "input"))
      (node (ref "R44") (pin "2") (pinfunction "2_2") (pintype "passive"))
      (node (ref "R45") (pin "1") (pinfunction "1_1") (pintype "passive"))
    )
    (net (code "81") (name "Net-(IC2-IN-)") (class "Default")
      (node (ref "IC2") (pin "3") (pinfunction "IN-_3") (pintype "input"))
      (node (ref "R42") (pin "1") (pinfunction "1_1") (pintype "passive"))
      (node (ref "R43") (pin "2") (pinfunction "2_2") (pintype "passive"))
    )
    (net (code "82") (name "Net-(IC3-IN+)") (class "Default")
      (node (ref "IC3") (pin "1") (pinfunction "IN+_1") (pintype "input"))
      (node (ref "R53") (pin "2") (pinfunction "2_2") (pintype "passive"))
      (node (ref "R54") (pin "1") (pinfunction "1_1") (pintype "passive"))
    )
    (net (code "83") (name "Net-(IC3-IN-)") (class "Default")
      (node (ref "IC3") (pin "3") (pinfunction "IN-_3") (pintype "input"))
      (node (ref "R34") (pin "1") (pinfunction "1_1") (pintype "passive"))
      (node (ref "R52") (pin "2") (pinfunction "2_2") (pintype "passive"))
    )
    (net (code "84") (name "Net-(IC4-IN+)") (class "Default")
      (node (ref "IC4") (pin "1") (pinfunction "IN+_1") (pintype "input"))
      (node (ref "R58") (pin "2") (pinfunction "2_2") (pintype "passive"))
      (node (ref "R59") (pin "1") (pinfunction "1_1") (pintype "passive"))
    )
    (net (code "85") (name "Net-(IC4-IN-)") (class "Default")
      (node (ref "IC4") (pin "3") (pinfunction "IN-_3") (pintype "input"))
      (node (ref "R56") (pin "1") (pinfunction "1_1") (pintype "passive"))
      (node (ref "R57") (pin "2") (pinfunction "2_2") (pintype "passive"))
    )
    (net (code "86") (name "Net-(IC5-FG)") (class "Default")
      (node (ref "IC5") (pin "1") (pinfunction "FG_1") (pintype "input"))
      (node (ref "RF1") (pin "2") (pinfunction "2_2") (pintype "passive"))
      (node (ref "RG1") (pin "2") (pinfunction "2_2") (pintype "passive"))
    )
    (net (code "87") (name "Net-(IC5-REF)") (class "Default")
      (node (ref "IC5") (pin "5") (pinfunction "REF_5") (pintype "input"))
      (node (ref "RG1") (pin "1") (pinfunction "1_1") (pintype "passive"))
      (node (ref "RZ1") (pin "S") (pinfunction "S_S") (pintype "passive"))
    )
    (net (code "88") (name "Net-(IC6-IN+)") (class "Default")
      (node (ref "C20") (pin "1") (pinfunction "1_1") (pintype "passive"))
      (node (ref "IC6") (pin "1") (pinfunction "IN+_1") (pintype "input"))
      (node (ref "R40") (pin "1") (pinfunction "1_1") (pintype "passive"))
    )
    (net (code "89") (name "Net-(IC7-IN+)") (class "Default")
      (node (ref "C23") (pin "1") (pinfunction "1_1") (pintype "passive"))
      (node (ref "IC7") (pin "1") (pinfunction "IN+_1") (pintype "input"))
      (node (ref "R47") (pin "1") (pinfunction "1_1") (pintype "passive"))
    )
    (net (code "90") (name "Net-(IC8-IN+)") (class "Default")
      (node (ref "C26") (pin "1") (pinfunction "1_1") (pintype "passive"))
      (node (ref "IC8") (pin "1") (pinfunction "IN+_1") (pintype "input"))
      (node (ref "R49") (pin "1") (pinfunction "1_1") (pintype "passive"))
    )
    (net (code "91") (name "Net-(IC9-IN+)") (class "Default")
      (node (ref "C29") (pin "1") (pinfunction "1_1") (pintype "passive"))
      (node (ref "IC9") (pin "1") (pinfunction "IN+_1") (pintype "input"))
      (node (ref "R51") (pin "1") (pinfunction "1_1") (pintype "passive"))
    )
    (net (code "92") (name "Net-(IC10-FG)") (class "Default")
      (node (ref "IC10") (pin "1") (pinfunction "FG_1") (pintype "input"))
      (node (ref "RF2") (pin "2") (pinfunction "2_2") (pintype "passive"))
      (node (ref "RG2") (pin "2") (pinfunction "2_2") (pintype "passive"))
    )
    (net (code "93") (name "Net-(IC10-REF)") (class "Default")
      (node (ref "IC10") (pin "5") (pinfunction "REF_5") (pintype "input"))
      (node (ref "RG2") (pin "1") (pinfunction "1_1") (pintype "passive"))
      (node (ref "RZ2") (pin "S") (pinfunction "S_S") (pintype "passive"))
    )
    (net (code "94") (name "Net-(IC11-FG)") (class "Default")
      (node (ref "IC11") (pin "1") (pinfunction "FG_1") (pintype "input"))
      (node (ref "RF3") (pin "2") (pinfunction "2_2") (pintype "passive"))
      (node (ref "RG3") (pin "2") (pinfunction "2_2") (pintype "passive"))
    )
    (net (code "95") (name "Net-(IC11-REF)") (class "Default")
      (node (ref "IC11") (pin "5") (pinfunction "REF_5") (pintype "input"))
      (node (ref "RG3") (pin "1") (pinfunction "1_1") (pintype "passive"))
      (node (ref "RZ3") (pin "S") (pinfunction "S_S") (pintype "passive"))
    )
    (net (code "96") (name "Net-(IC12-FG)") (class "Default")
      (node (ref "IC12") (pin "1") (pinfunction "FG_1") (pintype "input"))
      (node (ref "RF4") (pin "2") (pinfunction "2_2") (pintype "passive"))
      (node (ref "RG4") (pin "2") (pinfunction "2_2") (pintype "passive"))
    )
    (net (code "97") (name "Net-(IC12-REF)") (class "Default")
      (node (ref "IC12") (pin "5") (pinfunction "REF_5") (pintype "input"))
      (node (ref "RG4") (pin "1") (pinfunction "1_1") (pintype "passive"))
      (node (ref "RZ4") (pin "S") (pinfunction "S_S") (pintype "passive"))
    )
    (net (code "98") (name "Net-(IC13-IN+)") (class "Default")
      (node (ref "C36") (pin "1") (pinfunction "1_1") (pintype "passive"))
      (node (ref "IC13") (pin "1") (pinfunction "IN+_1") (pintype "input"))
      (node (ref "R12") (pin "1") (pinfunction "1_1") (pintype "passive"))
    )
    (net (code "99") (name "Net-(IC13-IN-)") (class "Default")
      (node (ref "IC13") (pin "3") (pinfunction "IN-_3") (pintype "input"))
      (node (ref "LC1") (pin "2") (pinfunction "2_2") (pintype "passive"))
      (node (ref "R13") (pin "2") (pinfunction "2_2") (pintype "passive"))
      (node (ref "R14") (pin "1") (pinfunction "1_1") (pintype "passive"))
    )
    (net (code "100") (name "Net-(IC13-OUT)") (class "Default")
      (node (ref "C11") (pin "2") (pinfunction "2_2") (pintype "passive"))
      (node (ref "IC13") (pin "4") (pinfunction "OUT_4") (pintype "output"))
      (node (ref "R13") (pin "1") (pinfunction "1_1") (pintype "passive"))
    )
    (net (code "101") (name "Net-(IC14-IN+)") (class "Default")
      (node (ref "C38") (pin "1") (pinfunction "1_1") (pintype "passive"))
      (node (ref "IC14") (pin "1") (pinfunction "IN+_1") (pintype "input"))
      (node (ref "R16") (pin "1") (pinfunction "1_1") (pintype "passive"))
    )
    (net (code "102") (name "Net-(IC14-IN-)") (class "Default")
      (node (ref "IC14") (pin "3") (pinfunction "IN-_3") (pintype "input"))
      (node (ref "LC2") (pin "2") (pinfunction "2_2") (pintype "passive"))
      (node (ref "R17") (pin "2") (pinfunction "2_2") (pintype "passive"))
      (node (ref "R18") (pin "1") (pinfunction "1_1") (pintype "passive"))
    )
    (net (code "103") (name "Net-(IC14-OUT)") (class "Default")
      (node (ref "C39") (pin "2") (pinfunction "2_2") (pintype "passive"))
      (node (ref "IC14") (pin "4") (pinfunction "OUT_4") (pintype "output"))
      (node (ref "R17") (pin "1") (pinfunction "1_1") (pintype "passive"))
    )
    (net (code "104") (name "Net-(IC15-IN+)") (class "Default")
      (node (ref "C41") (pin "1") (pinfunction "1_1") (pintype "passive"))
      (node (ref "IC15") (pin "1") (pinfunction "IN+_1") (pintype "input"))
      (node (ref "R20") (pin "1") (pinfunction "1_1") (pintype "passive"))
    )
    (net (code "105") (name "Net-(IC15-IN-)") (class "Default")
      (node (ref "IC15") (pin "3") (pinfunction "IN-_3") (pintype "input"))
      (node (ref "LC3") (pin "2") (pinfunction "2_2") (pintype "passive"))
      (node (ref "R21") (pin "2") (pinfunction "2_2") (pintype "passive"))
      (node (ref "R22") (pin "1") (pinfunction "1_1") (pintype "passive"))
    )
    (net (code "106") (name "Net-(IC15-OUT)") (class "Default")
      (node (ref "C42") (pin "2") (pinfunction "2_2") (pintype "passive"))
      (node (ref "IC15") (pin "4") (pinfunction "OUT_4") (pintype "output"))
      (node (ref "R21") (pin "1") (pinfunction "1_1") (pintype "passive"))
    )
    (net (code "107") (name "Net-(IC16-IN+)") (class "Default")
      (node (ref "C44") (pin "1") (pinfunction "1_1") (pintype "passive"))
      (node (ref "IC16") (pin "1") (pinfunction "IN+_1") (pintype "input"))
      (node (ref "R24") (pin "1") (pinfunction "1_1") (pintype "passive"))
    )
    (net (code "108") (name "Net-(IC16-IN-)") (class "Default")
      (node (ref "IC16") (pin "3") (pinfunction "IN-_3") (pintype "input"))
      (node (ref "LC4") (pin "2") (pinfunction "2_2") (pintype "passive"))
      (node (ref "R60") (pin "2") (pinfunction "2_2") (pintype "passive"))
      (node (ref "R61") (pin "1") (pinfunction "1_1") (pintype "passive"))
    )
    (net (code "109") (name "Net-(IC16-OUT)") (class "Default")
      (node (ref "C45") (pin "2") (pinfunction "2_2") (pintype "passive"))
      (node (ref "IC16") (pin "4") (pinfunction "OUT_4") (pintype "output"))
      (node (ref "R60") (pin "1") (pinfunction "1_1") (pintype "passive"))
    )
    (net (code "110") (name "Net-(IC17-IN+)") (class "Default")
      (node (ref "C47") (pin "1") (pinfunction "1_1") (pintype "passive"))
      (node (ref "IC17") (pin "1") (pinfunction "IN+_1") (pintype "input"))
      (node (ref "R63") (pin "1") (pinfunction "1_1") (pintype "passive"))
    )
    (net (code "111") (name "Net-(IC17-IN-)") (class "Default")
      (node (ref "IC17") (pin "3") (pinfunction "IN-_3") (pintype "input"))
      (node (ref "LC5") (pin "2") (pinfunction "2_2") (pintype "passive"))
      (node (ref "R64") (pin "2") (pinfunction "2_2") (pintype "passive"))
      (node (ref "R65") (pin "1") (pinfunction "1_1") (pintype "passive"))
    )
    (net (code "112") (name "Net-(IC17-OUT)") (class "Default")
      (node (ref "C48") (pin "2") (pinfunction "2_2") (pintype "passive"))
      (node (ref "IC17") (pin "4") (pinfunction "OUT_4") (pintype "output"))
      (node (ref "R64") (pin "1") (pinfunction "1_1") (pintype "passive"))
    )
    (net (code "113") (name "Net-(LCIN1-Pad1)") (class "Default")
      (node (ref "LCIN1") (pin "1") (pinfunction "1_1") (pintype "passive"))
      (node (ref "R11") (pin "2") (pinfunction "2_2") (pintype "passive"))
    )
    (net (code "114") (name "Net-(LCIN2-Pad1)") (class "Default")
      (node (ref "LCIN2") (pin "1") (pinfunction "1_1") (pintype "passive"))
      (node (ref "R15") (pin "2") (pinfunction "2_2") (pintype "passive"))
    )
    (net (code "115") (name "Net-(LCIN3-Pad1)") (class "Default")
      (node (ref "LCIN3") (pin "1") (pinfunction "1_1") (pintype "passive"))
      (node (ref "R19") (pin "2") (pinfunction "2_2") (pintype "passive"))
    )
    (net (code "116") (name "Net-(LCIN4-Pad1)") (class "Default")
      (node (ref "LCIN4") (pin "1") (pinfunction "1_1") (pintype "passive"))
      (node (ref "R23") (pin "2") (pinfunction "2_2") (pintype "passive"))
    )
    (net (code "117") (name "Net-(LCIN5-Pad1)") (class "Default")
      (node (ref "LCIN5") (pin "1") (pinfunction "1_1") (pintype "passive"))
      (node (ref "R62") (pin "2") (pinfunction "2_2") (pintype "passive"))
    )
    (net (code "118") (name "Net-(R10-Pad1)") (class "Default")
      (node (ref "R10") (pin "1") (pinfunction "1_1") (pintype "passive"))
      (node (ref "R9") (pin "2") (pinfunction "2_2") (pintype "passive"))
      (node (ref "U$5") (pin "G") (pinfunction "G_G") (pintype "passive"))
    )
    (net (code "119") (name "Net-(SOLENOIDS2B-2-PadA2)") (class "Default")
      (node (ref "SOLENOIDS2") (pin "A2") (pinfunction "2_A2") (pintype "bidirectional"))
      (node (ref "SOLENOIDS2") (pin "B2") (pinfunction "2_B2") (pintype "bidirectional"))
    )
    (net (code "120") (name "Net-(U$2-G)") (class "Default")
      (node (ref "R1") (pin "2") (pinfunction "2_2") (pintype "passive"))
      (node (ref "R2") (pin "1") (pinfunction "1_1") (pintype "passive"))
      (node (ref "U$2") (pin "1") (pinfunction "G_1") (pintype "passive"))
    )
    (net (code "121") (name "Net-(U$3-G)") (class "Default")
      (node (ref "R3") (pin "2") (pinfunction "2_2") (pintype "passive"))
      (node (ref "R4") (pin "1") (pinfunction "1_1") (pintype "passive"))
      (node (ref "U$3") (pin "1") (pinfunction "G_1") (pintype "passive"))
    )
    (net (code "122") (name "Net-(U$8-G)") (class "Default")
      (node (ref "R5") (pin "2") (pinfunction "2_2") (pintype "passive"))
      (node (ref "R6") (pin "1") (pinfunction "1_1") (pintype "passive"))
      (node (ref "U$8") (pin "1") (pinfunction "G_1") (pintype "passive"))
    )
    (net (code "123") (name "Net-(U$9-G)") (class "Default")
      (node (ref "R7") (pin "2") (pinfunction "2_2") (pintype "passive"))
      (node (ref "R8") (pin "1") (pinfunction "1_1") (pintype "passive"))
      (node (ref "U$9") (pin "1") (pinfunction "G_1") (pintype "passive"))
    )
    (net (code "124") (name "Net-(U6-O)") (class "Default")
      (node (ref "D5") (pin "A") (pinfunction "A_A") (pintype "passive"))
      (node (ref "U6") (pin "1") (pinfunction "O_1") (pintype "passive"))
    )
    (net (code "125") (name "PT1_PREC") (class "Default")
      (node (ref "IC1") (pin "4") (pinfunction "OUT_4") (pintype "output"))
      (node (ref "R37") (pin "1") (pinfunction "1_1") (pintype "passive"))
      (node (ref "R41") (pin "2") (pinfunction "2_2") (pintype "passive"))
    )
    (net (code "126") (name "PT1_VS-") (class "Default")
      (node (ref "PT1/2") (pin "A2") (pinfunction "2_A2") (pintype "bidirectional"))
      (node (ref "PT1/2") (pin "B2") (pinfunction "2_B2") (pintype "bidirectional"))
      (node (ref "R31") (pin "2") (pinfunction "2_2") (pintype "passive"))
      (node (ref "R36") (pin "2") (pinfunction "2_2") (pintype "passive"))
    )
    (net (code "127") (name "PT2_PREC") (class "Default")
      (node (ref "IC2") (pin "4") (pinfunction "OUT_4") (pintype "output"))
      (node (ref "R43") (pin "1") (pinfunction "1_1") (pintype "passive"))
      (node (ref "R46") (pin "2") (pinfunction "2_2") (pintype "passive"))
    )
    (net (code "128") (name "PT2_VS-") (class "Default")
      (node (ref "PT1/2") (pin "A4") (pinfunction "4_A4") (pintype "bidirectional"))
      (node (ref "PT1/2") (pin "B4") (pinfunction "4_B4") (pintype "bidirectional"))
      (node (ref "R32") (pin "2") (pinfunction "2_2") (pintype "passive"))
      (node (ref "R42") (pin "2") (pinfunction "2_2") (pintype "passive"))
    )
    (net (code "129") (name "PT3_PREC") (class "Default")
      (node (ref "IC3") (pin "4") (pinfunction "OUT_4") (pintype "output"))
      (node (ref "R48") (pin "2") (pinfunction "2_2") (pintype "passive"))
      (node (ref "R52") (pin "1") (pinfunction "1_1") (pintype "passive"))
    )
    (net (code "130") (name "PT3_VS-") (class "Default")
      (node (ref "PT3/4") (pin "A2") (pinfunction "2_A2") (pintype "bidirectional"))
      (node (ref "PT3/4") (pin "B2") (pinfunction "2_B2") (pintype "bidirectional"))
      (node (ref "R33") (pin "2") (pinfunction "2_2") (pintype "passive"))
      (node (ref "R34") (pin "2") (pinfunction "2_2") (pintype "passive"))
    )
    (net (code "131") (name "PT4_PREC") (class "Default")
      (node (ref "IC4") (pin "4") (pinfunction "OUT_4") (pintype "output"))
      (node (ref "R50") (pin "2") (pinfunction "2_2") (pintype "passive"))
      (node (ref "R57") (pin "1") (pinfunction "1_1") (pintype "passive"))
    )
    (net (code "132") (name "PT4_VS-") (class "Default")
      (node (ref "PT3/4") (pin "A4") (pinfunction "4_A4") (pintype "bidirectional"))
      (node (ref "PT3/4") (pin "B4") (pinfunction "4_B4") (pintype "bidirectional"))
      (node (ref "R55") (pin "2") (pinfunction "2_2") (pintype "passive"))
      (node (ref "R56") (pin "2") (pinfunction "2_2") (pintype "passive"))
    )
    (net (code "133") (name "RELAY_NEGATIVE") (class "Default")
      (node (ref "D1") (pin "A") (pinfunction "A_A") (pintype "passive"))
      (node (ref "SOL+RELAY") (pin "A1") (pinfunction "1_A1") (pintype "bidirectional"))
      (node (ref "SOL+RELAY") (pin "B1") (pinfunction "1_B1") (pintype "bidirectional"))
      (node (ref "U$2") (pin "3") (pinfunction "D_3") (pintype "passive"))
    )
    (net (code "134") (name "SCLK") (class "Default")
      (node (ref "ADC1") (pin "13") (pinfunction "CLK_13") (pintype "bidirectional"))
      (node (ref "ADC2") (pin "13") (pinfunction "CLK_13") (pintype "bidirectional"))
      (node (ref "ADC3") (pin "13") (pinfunction "CLK_13") (pintype "bidirectional"))
      (node (ref "RPI_DEBUG") (pin "7") (pinfunction "1_7") (pintype "passive"))
      (node (ref "RPI_GPIO") (pin "23") (pinfunction "KL_23") (pintype "passive"))
    )
    (net (code "135") (name "SOLENOID_1_NEGATIVE") (class "Default")
      (node (ref "D2") (pin "A") (pinfunction "A_A") (pintype "passive"))
      (node (ref "SOL+RELAY") (pin "A2") (pinfunction "2_A2") (pintype "bidirectional"))
      (node (ref "SOL+RELAY") (pin "B2") (pinfunction "2_B2") (pintype "bidirectional"))
      (node (ref "U$3") (pin "3") (pinfunction "D_3") (pintype "passive"))
    )
    (net (code "136") (name "SOLENOID_2_NEGATIVE") (class "Default")
      (node (ref "D3") (pin "A") (pinfunction "A_A") (pintype "passive"))
      (node (ref "SOLENOIDS") (pin "A1") (pinfunction "1_A1") (pintype "bidirectional"))
      (node (ref "SOLENOIDS") (pin "B1") (pinfunction "1_B1") (pintype "bidirectional"))
      (node (ref "U$8") (pin "3") (pinfunction "D_3") (pintype "passive"))
    )
    (net (code "137") (name "SOLENOID_3_NEGATIVE") (class "Default")
      (node (ref "D4") (pin "A") (pinfunction "A_A") (pintype "passive"))
      (node (ref "SOLENOIDS") (pin "A2") (pinfunction "2_A2") (pintype "bidirectional"))
      (node (ref "SOLENOIDS") (pin "B2") (pinfunction "2_B2") (pintype "bidirectional"))
      (node (ref "U$9") (pin "3") (pinfunction "D_3") (pintype "passive"))
    )
    (net (code "138") (name "SOLENOID_4_NEGATIVE") (class "Default")
      (node (ref "D6") (pin "A") (pinfunction "A_A") (pintype "passive"))
      (node (ref "SOLENOIDS2") (pin "A1") (pinfunction "1_A1") (pintype "bidirectional"))
      (node (ref "SOLENOIDS2") (pin "B1") (pinfunction "1_B1") (pintype "bidirectional"))
      (node (ref "U$5") (pin "D") (pinfunction "D_D") (pintype "passive"))
    )
    (net (code "139") (name "unconnected-(LCIN5-Pad2)") (class "Default")
      (node (ref "LCIN5") (pin "2") (pinfunction "2_2") (pintype "passive"))
    )
    (net (code "140") (name "unconnected-(RPI_GPIOA-KL-Pad1)") (class "Default")
      (node (ref "RPI_GPIO") (pin "1") (pinfunction "KL_1") (pintype "passive"))
    )
    (net (code "141") (name "unconnected-(RPI_GPIOAA-KL-Pad33)") (class "Default")
      (node (ref "RPI_GPIO") (pin "33") (pinfunction "KL_33") (pintype "passive"))
    )
    (net (code "142") (name "unconnected-(RPI_GPIOAB-KL-Pad34)") (class "Default")
      (node (ref "RPI_GPIO") (pin "34") (pinfunction "KL_34") (pintype "passive"))
    )
    (net (code "143") (name "unconnected-(RPI_GPIOAC-KL-Pad35)") (class "Default")
      (node (ref "RPI_GPIO") (pin "35") (pinfunction "KL_35") (pintype "passive"))
    )
    (net (code "144") (name "unconnected-(RPI_GPIOAD-KL-Pad36)") (class "Default")
      (node (ref "RPI_GPIO") (pin "36") (pinfunction "KL_36") (pintype "passive"))
    )
    (net (code "145") (name "unconnected-(RPI_GPIOAE-KL-Pad37)") (class "Default")
      (node (ref "RPI_GPIO") (pin "37") (pinfunction "KL_37") (pintype "passive"))
    )
    (net (code "146") (name "unconnected-(RPI_GPIOAF-KL-Pad38)") (class "Default")
      (node (ref "RPI_GPIO") (pin "38") (pinfunction "KL_38") (pintype "passive"))
    )
    (net (code "147") (name "unconnected-(RPI_GPIOAG-KL-Pad39)") (class "Default")
      (node (ref "RPI_GPIO") (pin "39") (pinfunction "KL_39") (pintype "passive"))
    )
    (net (code "148") (name "unconnected-(RPI_GPIOAH-KL-Pad4)") (class "Default")
      (node (ref "RPI_GPIO") (pin "4") (pinfunction "KL_4") (pintype "passive"))
    )
    (net (code "149") (name "unconnected-(RPI_GPIOAI-KL-Pad40)") (class "Default")
      (node (ref "RPI_GPIO") (pin "40") (pinfunction "KL_40") (pintype "passive"))
    )
    (net (code "150") (name "unconnected-(RPI_GPIOAJ-KL-Pad5)") (class "Default")
      (node (ref "RPI_GPIO") (pin "5") (pinfunction "KL_5") (pintype "passive"))
    )
    (net (code "151") (name "unconnected-(RPI_GPIOAL-KL-Pad7)") (class "Default")
      (node (ref "RPI_GPIO") (pin "7") (pinfunction "KL_7") (pintype "passive"))
    )
    (net (code "152") (name "unconnected-(RPI_GPIOAM-KL-Pad8)") (class "Default")
      (node (ref "RPI_GPIO") (pin "8") (pinfunction "KL_8") (pintype "passive"))
    )
    (net (code "153") (name "unconnected-(RPI_GPIOAN-KL-Pad9)") (class "Default")
      (node (ref "RPI_GPIO") (pin "9") (pinfunction "KL_9") (pintype "passive"))
    )
    (net (code "154") (name "unconnected-(RPI_GPIOB-KL-Pad10)") (class "Default")
      (node (ref "RPI_GPIO") (pin "10") (pinfunction "KL_10") (pintype "passive"))
    )
    (net (code "155") (name "unconnected-(RPI_GPIOD-KL-Pad12)") (class "Default")
      (node (ref "RPI_GPIO") (pin "12") (pinfunction "KL_12") (pintype "passive"))
    )
    (net (code "156") (name "unconnected-(RPI_GPIOF-KL-Pad14)") (class "Default")
      (node (ref "RPI_GPIO") (pin "14") (pinfunction "KL_14") (pintype "passive"))
    )
    (net (code "157") (name "unconnected-(RPI_GPIOI-KL-Pad17)") (class "Default")
      (node (ref "RPI_GPIO") (pin "17") (pinfunction "KL_17") (pintype "passive"))
    )
    (net (code "158") (name "unconnected-(RPI_GPIOM-KL-Pad20)") (class "Default")
      (node (ref "RPI_GPIO") (pin "20") (pinfunction "KL_20") (pintype "passive"))
    )
    (net (code "159") (name "unconnected-(RPI_GPIOR-KL-Pad25)") (class "Default")
      (node (ref "RPI_GPIO") (pin "25") (pinfunction "KL_25") (pintype "passive"))
    )
    (net (code "160") (name "unconnected-(RPI_GPIOT-KL-Pad27)") (class "Default")
      (node (ref "RPI_GPIO") (pin "27") (pinfunction "KL_27") (pintype "passive"))
    )
    (net (code "161") (name "unconnected-(RPI_GPIOU-KL-Pad28)") (class "Default")
      (node (ref "RPI_GPIO") (pin "28") (pinfunction "KL_28") (pintype "passive"))
    )
    (net (code "162") (name "unconnected-(RPI_GPIOV-KL-Pad29)") (class "Default")
      (node (ref "RPI_GPIO") (pin "29") (pinfunction "KL_29") (pintype "passive"))
    )
    (net (code "163") (name "unconnected-(RPI_GPIOW-KL-Pad3)") (class "Default")
      (node (ref "RPI_GPIO") (pin "3") (pinfunction "KL_3") (pintype "passive"))
    )
    (net (code "164") (name "unconnected-(RPI_GPIOX-KL-Pad30)") (class "Default")
      (node (ref "RPI_GPIO") (pin "30") (pinfunction "KL_30") (pintype "passive"))
    )
    (net (code "165") (name "unconnected-(RPI_GPIOY-KL-Pad31)") (class "Default")
      (node (ref "RPI_GPIO") (pin "31") (pinfunction "KL_31") (pintype "passive"))
    )
    (net (code "166") (name "unconnected-(RPI_GPIOZ-KL-Pad32)") (class "Default")
      (node (ref "RPI_GPIO") (pin "32") (pinfunction "KL_32") (pintype "passive"))
    )
    (net (code "167") (name "unconnected-(U6-S-Pad3)") (class "Default")
      (node (ref "U6") (pin "3") (pinfunction "S_3") (pintype "passive"))
    )
  )
)
